# MotorControl_M4.net
KiCad netlist of a schematic drawn in EAGLE
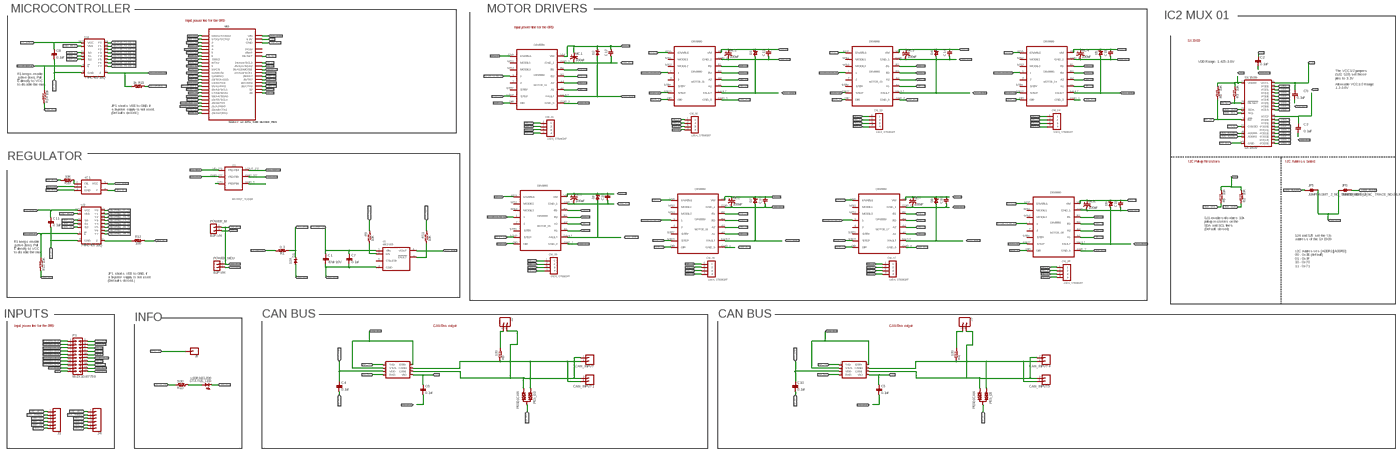
[diagram p0: schematic, sheet 1, overview]
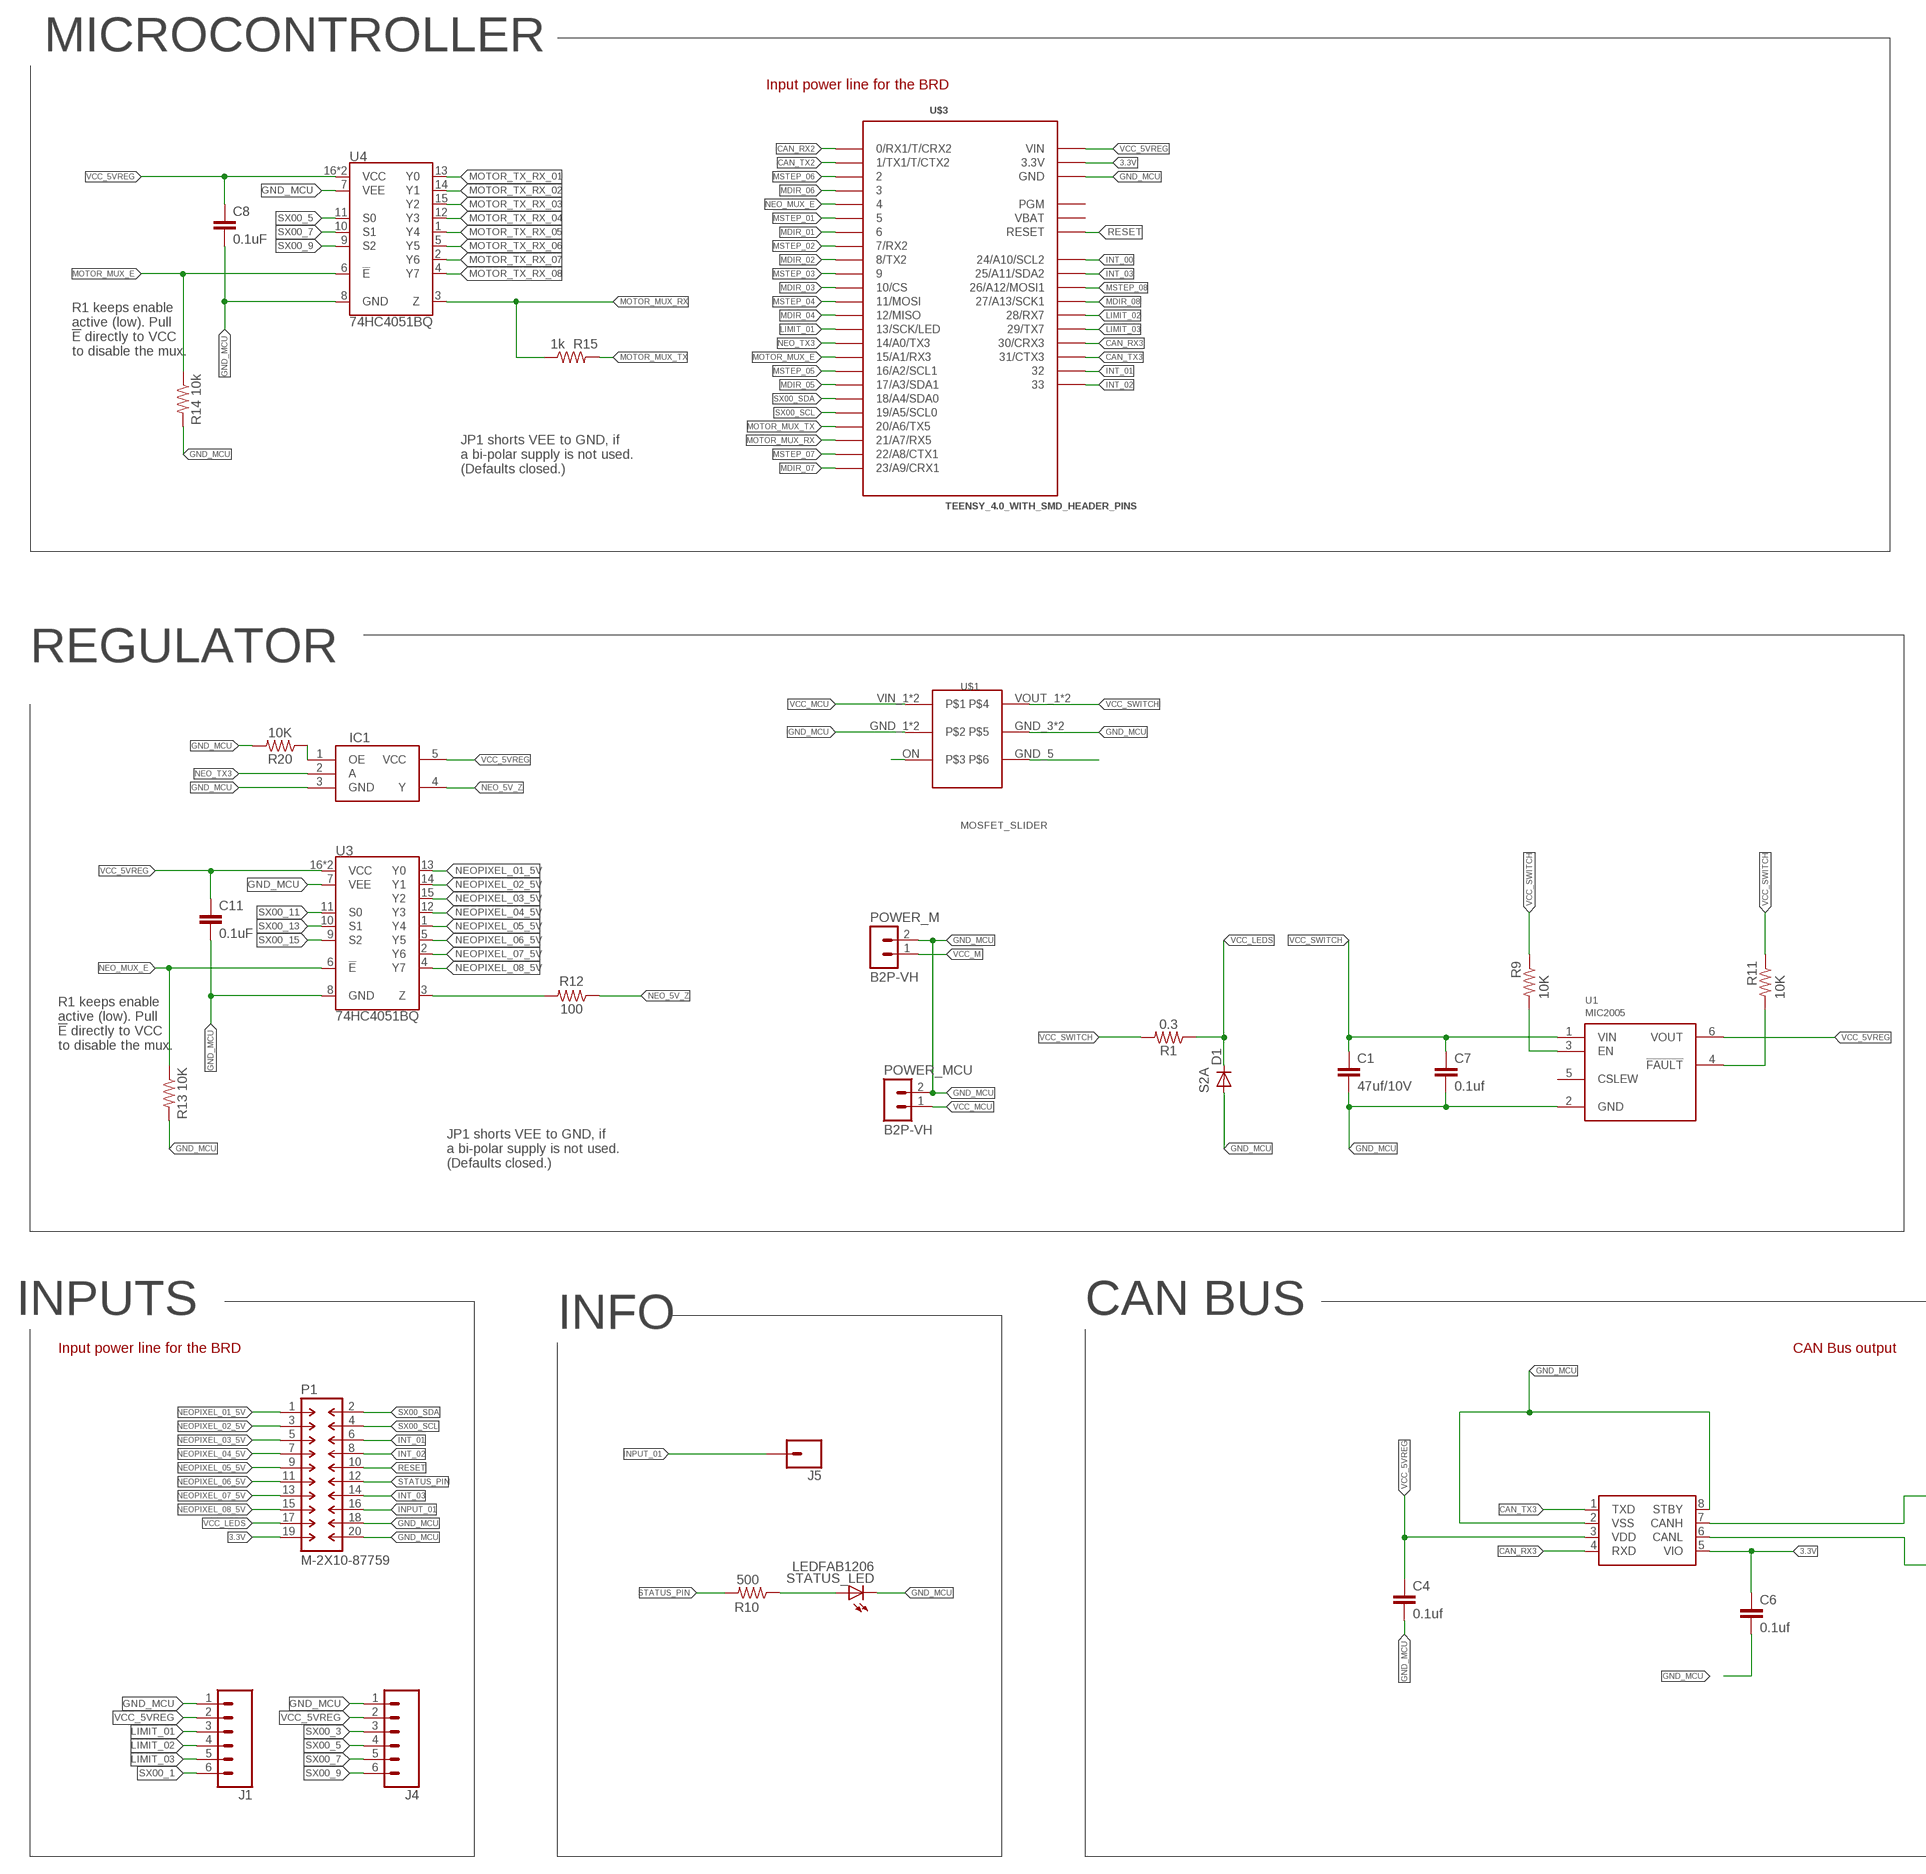
[diagram p1: schematic, sheet 1, part 1 of 4]
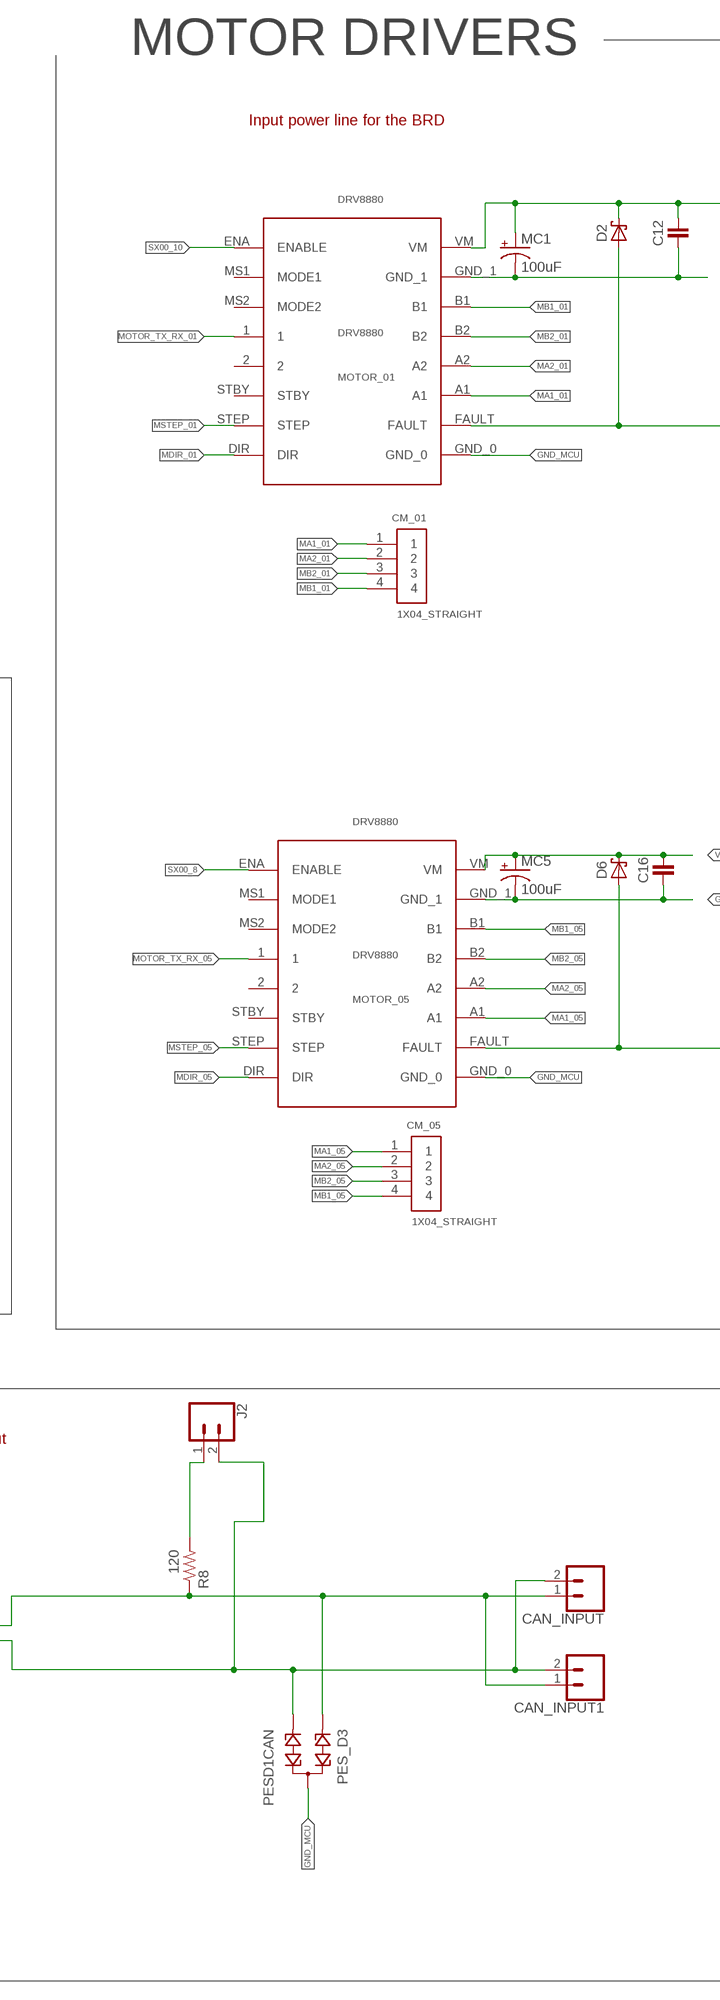
[diagram p2: schematic, sheet 1, part 2 of 4]
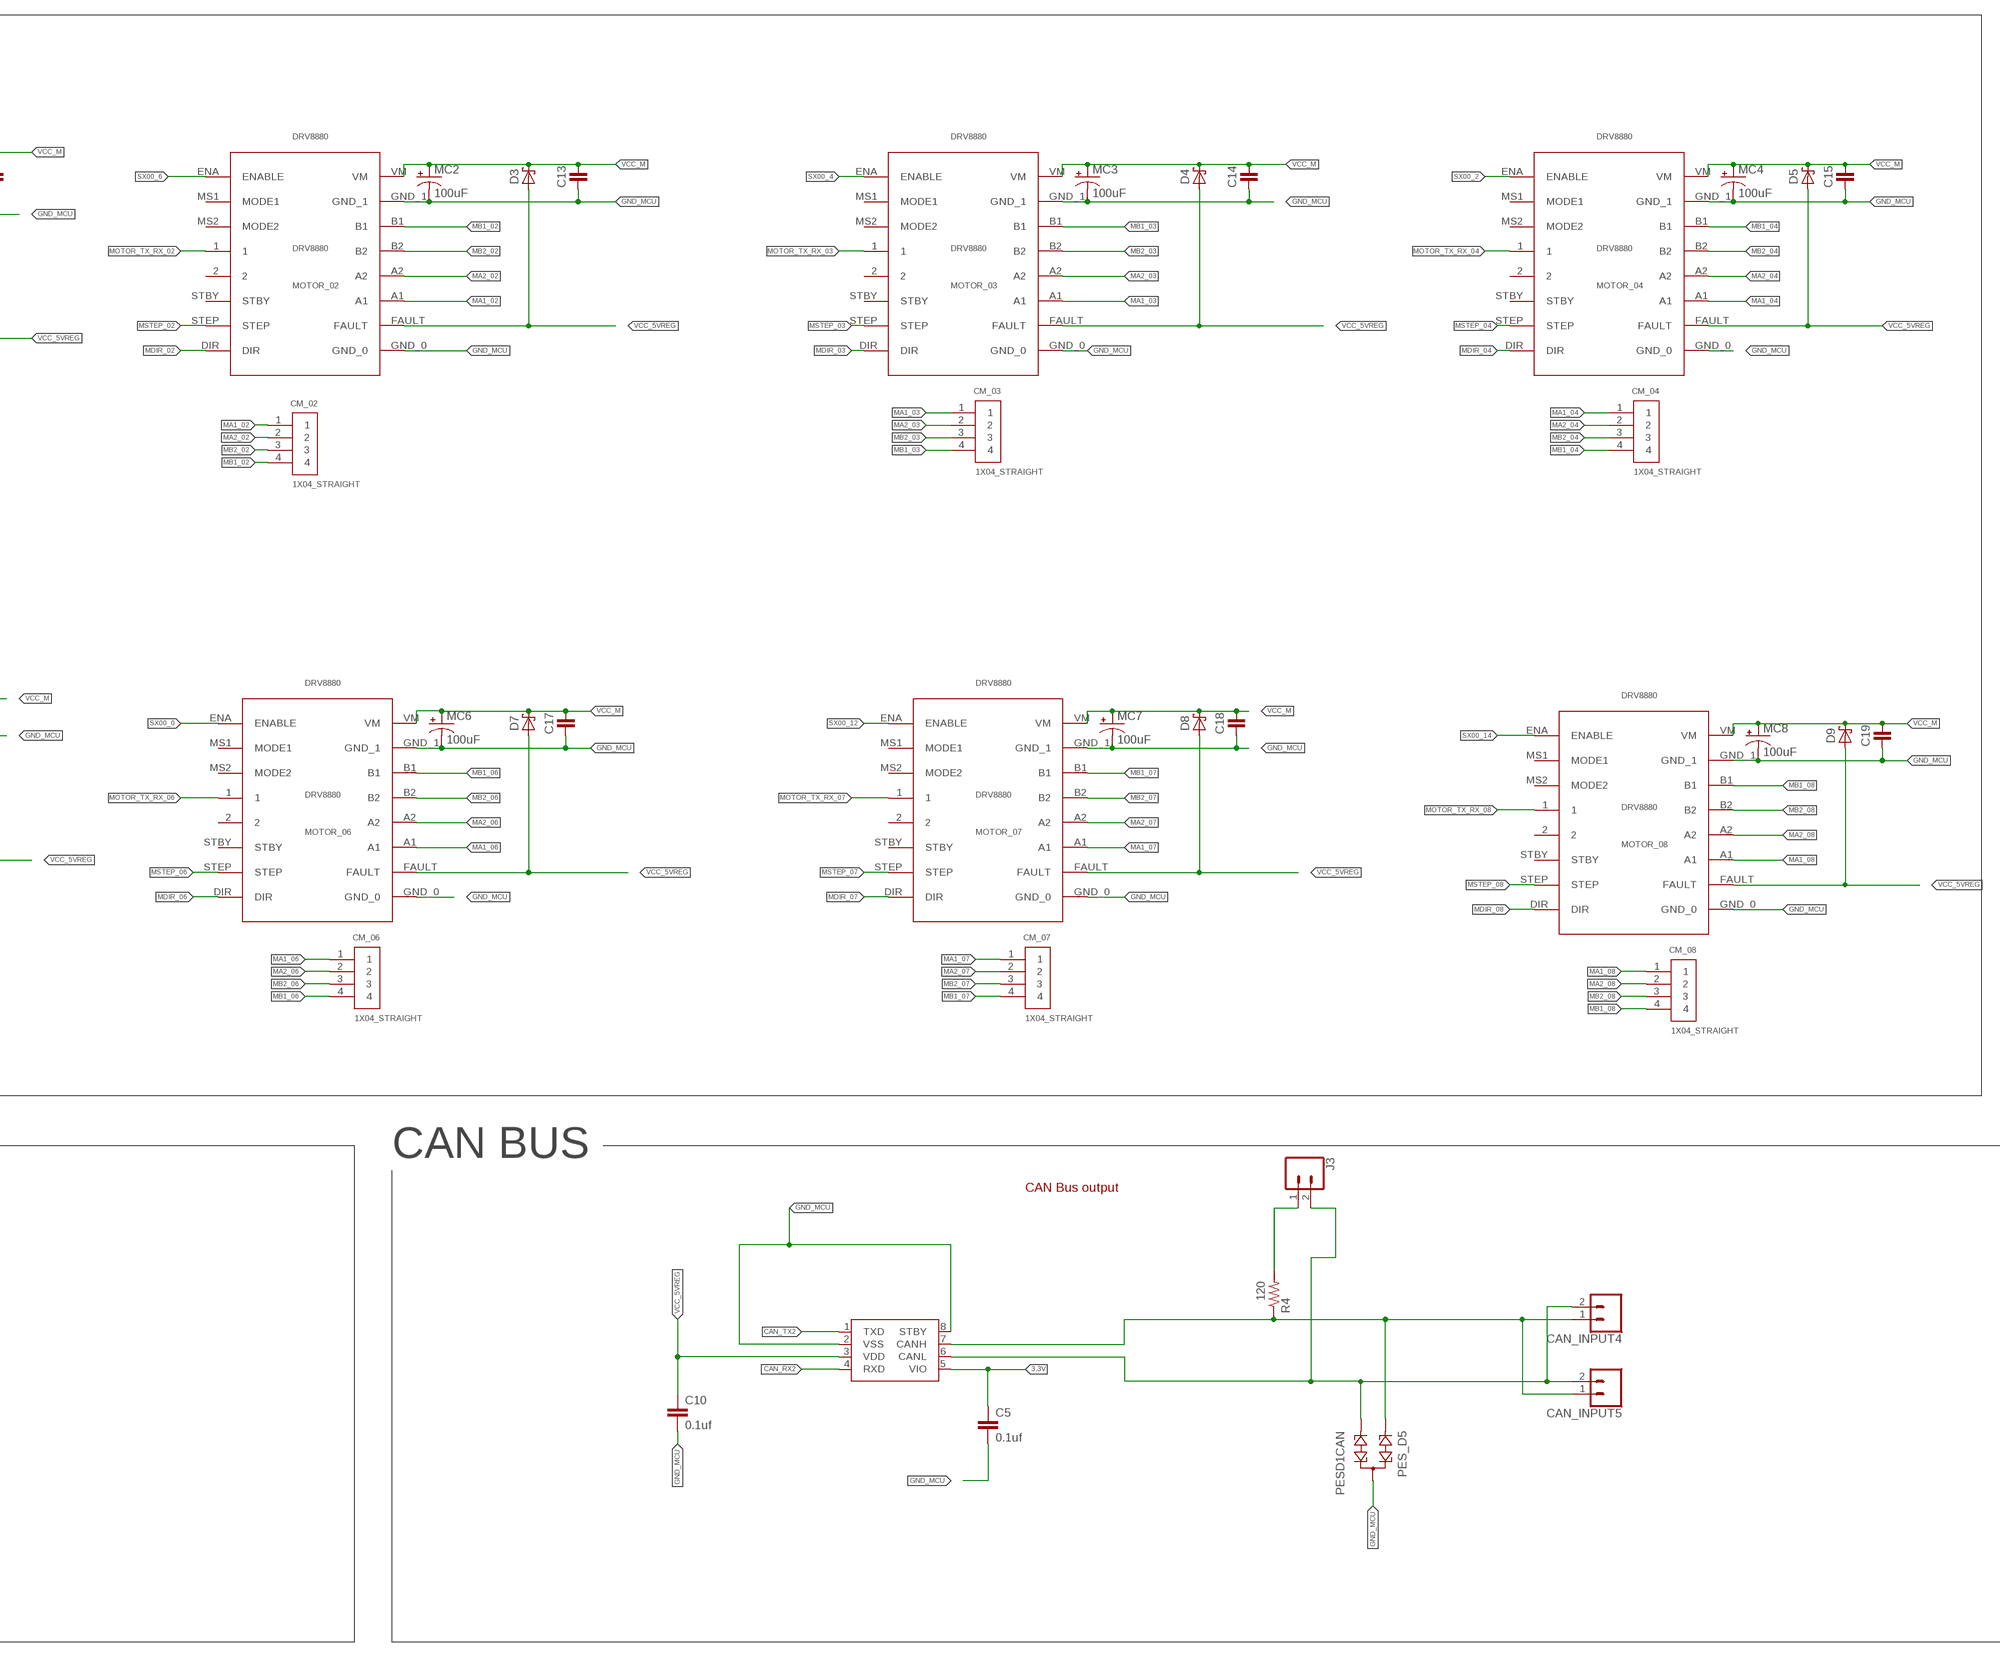
[diagram p3: schematic, sheet 1, part 3 of 4]
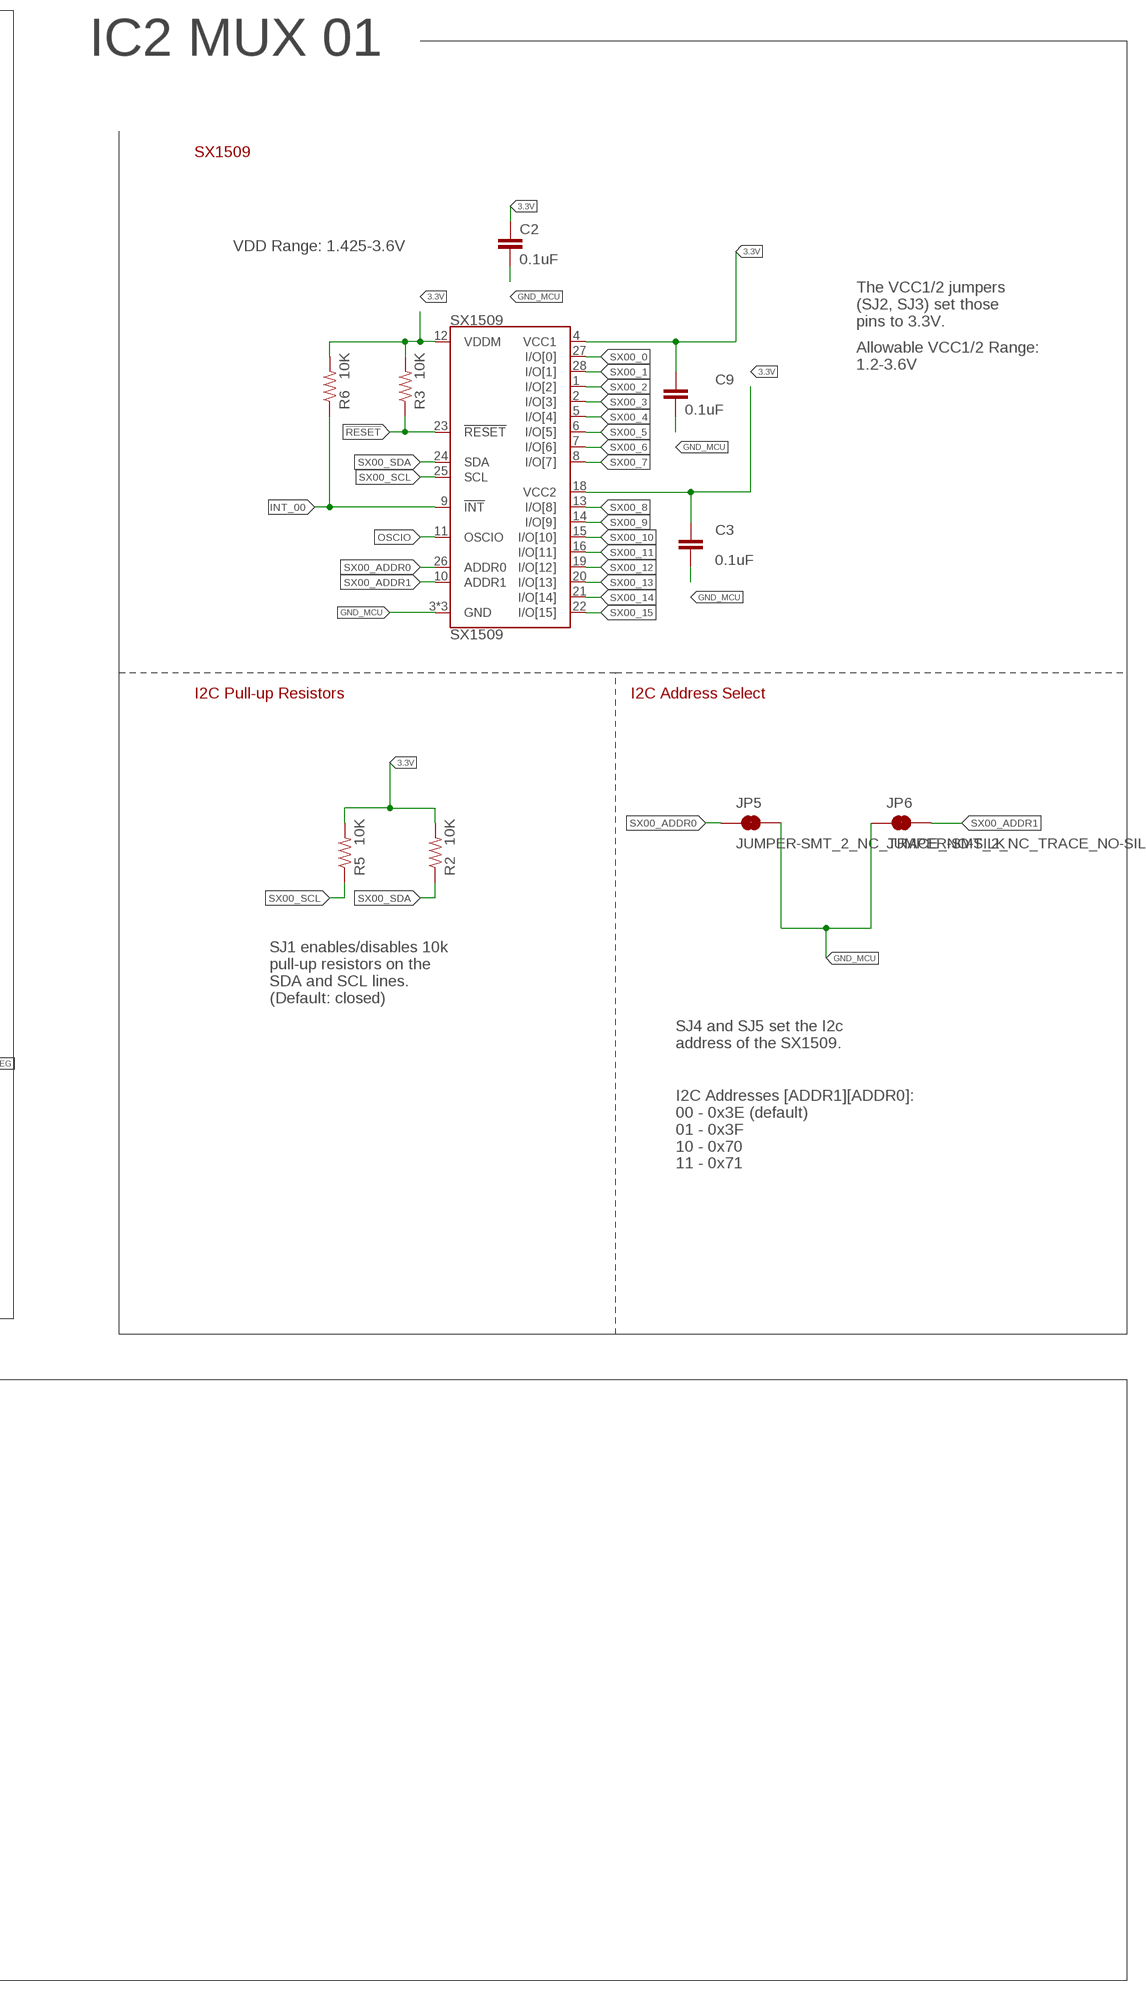
[diagram p4: schematic, sheet 1, part 4 of 4]

(export (version "E")
  (design (tool "Eeschema 10.0.6"))
  (components
    (comp (ref "C1")
      (value "47uf/10V")
      (footprint "eagle-import:0603-CAP")
      (libsource (lib "eagle-import") (part "0.1UF-25V(+80/-20%)(0603)"))
    )
    (comp (ref "C2")
      (value "0.1uF")
      (footprint "eagle-import:0603-CAP")
      (libsource (lib "eagle-import") (part "0.1UF-25V(+80/-20%)(0603)"))
    )
    (comp (ref "C3")
      (value "0.1uF")
      (footprint "eagle-import:0603-CAP")
      (libsource (lib "eagle-import") (part "0.1UF-25V(+80/-20%)(0603)"))
    )
    (comp (ref "C4")
      (value "0.1uf")
      (footprint "eagle-import:0603-CAP")
      (libsource (lib "eagle-import") (part "0.1UF-25V(+80/-20%)(0603)"))
    )
    (comp (ref "C5")
      (value "0.1uf")
      (footprint "eagle-import:0603-CAP")
      (libsource (lib "eagle-import") (part "0.1UF-25V(+80/-20%)(0603)"))
    )
    (comp (ref "C6")
      (value "0.1uf")
      (footprint "eagle-import:0603-CAP")
      (libsource (lib "eagle-import") (part "0.1UF-25V(+80/-20%)(0603)"))
    )
    (comp (ref "C7")
      (value "0.1uf")
      (footprint "eagle-import:0603-CAP")
      (libsource (lib "eagle-import") (part "0.1UF-25V(+80/-20%)(0603)"))
    )
    (comp (ref "C8")
      (value "0.1uF")
      (footprint "eagle-import:0603")
      (libsource (lib "eagle-import") (part "0.1UF-0603-25V-(+80/-20%)"))
    )
    (comp (ref "C9")
      (value "0.1uF")
      (footprint "eagle-import:0603-CAP")
      (libsource (lib "eagle-import") (part "0.1UF-25V(+80/-20%)(0603)"))
    )
    (comp (ref "C10")
      (value "0.1uf")
      (footprint "eagle-import:0603-CAP")
      (libsource (lib "eagle-import") (part "0.1UF-25V(+80/-20%)(0603)"))
    )
    (comp (ref "C11")
      (value "0.1uF")
      (footprint "eagle-import:0603")
      (libsource (lib "eagle-import") (part "0.1UF-0603-25V-(+80/-20%)"))
    )
    (comp (ref "C12")
      (value "CAPACITOR-1210")
      (footprint "eagle-import:C1210")
      (libsource (lib "eagle-import") (part "CAPACITOR-1210"))
    )
    (comp (ref "C13")
      (value "CAPACITOR-1210")
      (footprint "eagle-import:C1210")
      (libsource (lib "eagle-import") (part "CAPACITOR-1210"))
    )
    (comp (ref "C14")
      (value "CAPACITOR-1210")
      (footprint "eagle-import:C1210")
      (libsource (lib "eagle-import") (part "CAPACITOR-1210"))
    )
    (comp (ref "C15")
      (value "CAPACITOR-1210")
      (footprint "eagle-import:C1210")
      (libsource (lib "eagle-import") (part "CAPACITOR-1210"))
    )
    (comp (ref "C16")
      (value "CAPACITOR-1210")
      (footprint "eagle-import:C1210")
      (libsource (lib "eagle-import") (part "CAPACITOR-1210"))
    )
    (comp (ref "C17")
      (value "CAPACITOR-1210")
      (footprint "eagle-import:C1210")
      (libsource (lib "eagle-import") (part "CAPACITOR-1210"))
    )
    (comp (ref "C18")
      (value "CAPACITOR-1210")
      (footprint "eagle-import:C1210")
      (libsource (lib "eagle-import") (part "CAPACITOR-1210"))
    )
    (comp (ref "C19")
      (value "CAPACITOR-1210")
      (footprint "eagle-import:C1210")
      (libsource (lib "eagle-import") (part "CAPACITOR-1210"))
    )
    (comp (ref "CAN_INPUT")
      (value "CONN_02-JST-2MM-SMT")
      (footprint "eagle-import:JST-2-SMD")
      (libsource (lib "eagle-import") (part "CONN_02-JST-2MM-SMT"))
    )
    (comp (ref "CAN_INPUT1")
      (value "CONN_02-JST-2MM-SMT")
      (footprint "eagle-import:JST-2-SMD")
      (libsource (lib "eagle-import") (part "CONN_02-JST-2MM-SMT"))
    )
    (comp (ref "CAN_INPUT4")
      (value "CONN_02-JST-2MM-SMT")
      (footprint "eagle-import:JST-2-SMD")
      (libsource (lib "eagle-import") (part "CONN_02-JST-2MM-SMT"))
    )
    (comp (ref "CAN_INPUT5")
      (value "CONN_02-JST-2MM-SMT")
      (footprint "eagle-import:JST-2-SMD")
      (libsource (lib "eagle-import") (part "CONN_02-JST-2MM-SMT"))
    )
    (comp (ref "CM_01")
      (value "1X04_STRAIGHT")
      (footprint "eagle-import:1X04-CLEANBIG")
      (libsource (lib "eagle-import") (part "1X4-CLEANBIG"))
    )
    (comp (ref "CM_02")
      (value "1X04_STRAIGHT")
      (footprint "eagle-import:1X04-CLEANBIG")
      (libsource (lib "eagle-import") (part "1X4-CLEANBIG"))
    )
    (comp (ref "CM_03")
      (value "1X04_STRAIGHT")
      (footprint "eagle-import:1X04-CLEANBIG")
      (libsource (lib "eagle-import") (part "1X4-CLEANBIG"))
    )
    (comp (ref "CM_04")
      (value "1X04_STRAIGHT")
      (footprint "eagle-import:1X04-CLEANBIG")
      (libsource (lib "eagle-import") (part "1X4-CLEANBIG"))
    )
    (comp (ref "CM_05")
      (value "1X04_STRAIGHT")
      (footprint "eagle-import:1X04-CLEANBIG")
      (libsource (lib "eagle-import") (part "1X4-CLEANBIG"))
    )
    (comp (ref "CM_06")
      (value "1X04_STRAIGHT")
      (footprint "eagle-import:1X04-CLEANBIG")
      (libsource (lib "eagle-import") (part "1X4-CLEANBIG"))
    )
    (comp (ref "CM_07")
      (value "1X04_STRAIGHT")
      (footprint "eagle-import:1X04-CLEANBIG")
      (libsource (lib "eagle-import") (part "1X4-CLEANBIG"))
    )
    (comp (ref "CM_08")
      (value "1X04_STRAIGHT")
      (footprint "eagle-import:1X04-CLEANBIG")
      (libsource (lib "eagle-import") (part "1X4-CLEANBIG"))
    )
    (comp (ref "D1")
      (value "S2A")
      (footprint "eagle-import:DO214AA")
      (fields (field (name "MF") "Fairchild"))
      (libsource (lib "eagle-import") (part "S2A"))
    )
    (comp (ref "D2")
      (value "D_SCHOTTKY-SOD123")
      (footprint "eagle-import:SOD123")
      (libsource (lib "eagle-import") (part "D_SCHOTTKY-SOD123"))
    )
    (comp (ref "D3")
      (value "D_SCHOTTKY-SOD123")
      (footprint "eagle-import:SOD123")
      (libsource (lib "eagle-import") (part "D_SCHOTTKY-SOD123"))
    )
    (comp (ref "D4")
      (value "D_SCHOTTKY-SOD123")
      (footprint "eagle-import:SOD123")
      (libsource (lib "eagle-import") (part "D_SCHOTTKY-SOD123"))
    )
    (comp (ref "D5")
      (value "D_SCHOTTKY-SOD123")
      (footprint "eagle-import:SOD123")
      (libsource (lib "eagle-import") (part "D_SCHOTTKY-SOD123"))
    )
    (comp (ref "D6")
      (value "D_SCHOTTKY-SOD123")
      (footprint "eagle-import:SOD123")
      (libsource (lib "eagle-import") (part "D_SCHOTTKY-SOD123"))
    )
    (comp (ref "D7")
      (value "D_SCHOTTKY-SOD123")
      (footprint "eagle-import:SOD123")
      (libsource (lib "eagle-import") (part "D_SCHOTTKY-SOD123"))
    )
    (comp (ref "D8")
      (value "D_SCHOTTKY-SOD123")
      (footprint "eagle-import:SOD123")
      (libsource (lib "eagle-import") (part "D_SCHOTTKY-SOD123"))
    )
    (comp (ref "D9")
      (value "D_SCHOTTKY-SOD123")
      (footprint "eagle-import:SOD123")
      (libsource (lib "eagle-import") (part "D_SCHOTTKY-SOD123"))
    )
    (comp (ref "IC1")
      (value "74AHC1G125FDBV")
      (footprint "eagle-import:SOT23-5")
      (libsource (lib "eagle-import") (part "741G125FDBVAHC"))
    )
    (comp (ref "J1")
      (value "CONN_06SMD-1MM")
      (footprint "eagle-import:1X06-1MM")
      (libsource (lib "eagle-import") (part "CONN_06SMD-1MM"))
    )
    (comp (ref "J2")
      (value "CONN_02")
      (footprint "eagle-import:1X02")
      (libsource (lib "eagle-import") (part "CONN_02"))
    )
    (comp (ref "J3")
      (value "CONN_02")
      (footprint "eagle-import:1X02")
      (libsource (lib "eagle-import") (part "CONN_02"))
    )
    (comp (ref "J4")
      (value "CONN_06SMD-1MM")
      (footprint "eagle-import:1X06-1MM")
      (libsource (lib "eagle-import") (part "CONN_06SMD-1MM"))
    )
    (comp (ref "J5")
      (value "CONN_01")
      (footprint "eagle-import:1X01")
      (libsource (lib "eagle-import") (part "CONN_01"))
    )
    (comp (ref "JP5")
      (value "JUMPER-SMT_2_NC_TRACE_NO-SILK")
      (footprint "eagle-import:SMT-JUMPER_2_NC_TRACE_NO-SILK")
      (libsource (lib "eagle-import") (part "JUMPER-SMT_2_NC_TRACE_NO-SILK"))
    )
    (comp (ref "JP6")
      (value "JUMPER-SMT_2_NC_TRACE_NO-SILK")
      (footprint "eagle-import:SMT-JUMPER_2_NC_TRACE_NO-SILK")
      (libsource (lib "eagle-import") (part "JUMPER-SMT_2_NC_TRACE_NO-SILK"))
    )
    (comp (ref "MC1")
      (value "100uF")
      (footprint "eagle-import:PANASONIC_D")
      (libsource (lib "eagle-import") (part "100UF-POLAR-25V-20%(ELEC)"))
    )
    (comp (ref "MC2")
      (value "100uF")
      (footprint "eagle-import:PANASONIC_D")
      (libsource (lib "eagle-import") (part "100UF-POLAR-25V-20%(ELEC)"))
    )
    (comp (ref "MC3")
      (value "100uF")
      (footprint "eagle-import:PANASONIC_D")
      (libsource (lib "eagle-import") (part "100UF-POLAR-25V-20%(ELEC)"))
    )
    (comp (ref "MC4")
      (value "100uF")
      (footprint "eagle-import:PANASONIC_D")
      (libsource (lib "eagle-import") (part "100UF-POLAR-25V-20%(ELEC)"))
    )
    (comp (ref "MC5")
      (value "100uF")
      (footprint "eagle-import:PANASONIC_D")
      (libsource (lib "eagle-import") (part "100UF-POLAR-25V-20%(ELEC)"))
    )
    (comp (ref "MC6")
      (value "100uF")
      (footprint "eagle-import:PANASONIC_D")
      (libsource (lib "eagle-import") (part "100UF-POLAR-25V-20%(ELEC)"))
    )
    (comp (ref "MC7")
      (value "100uF")
      (footprint "eagle-import:PANASONIC_D")
      (libsource (lib "eagle-import") (part "100UF-POLAR-25V-20%(ELEC)"))
    )
    (comp (ref "MC8")
      (value "100uF")
      (footprint "eagle-import:PANASONIC_D")
      (libsource (lib "eagle-import") (part "100UF-POLAR-25V-20%(ELEC)"))
    )
    (comp (ref "MCP2562FD")
      (value "MCP2562-E/SN")
      (footprint "eagle-import:SOIC127P600X175-8N")
      (fields (field (name "MF") "Microchip"))
      (libsource (lib "eagle-import") (part "MCP2562-E/SN"))
    )
    (comp (ref "MCP2562_2.0")
      (value "MCP2562-E/SN")
      (footprint "eagle-import:SOIC127P600X175-8N")
      (fields (field (name "MF") "Microchip"))
      (libsource (lib "eagle-import") (part "MCP2562-E/SN"))
    )
    (comp (ref "MOTOR_01")
      (value "DRV8880")
      (footprint "eagle-import:DRV8880")
      (libsource (lib "eagle-import") (part "DRV8880"))
    )
    (comp (ref "MOTOR_02")
      (value "DRV8880")
      (footprint "eagle-import:DRV8880")
      (libsource (lib "eagle-import") (part "DRV8880"))
    )
    (comp (ref "MOTOR_03")
      (value "DRV8880")
      (footprint "eagle-import:DRV8880")
      (libsource (lib "eagle-import") (part "DRV8880"))
    )
    (comp (ref "MOTOR_04")
      (value "DRV8880")
      (footprint "eagle-import:DRV8880")
      (libsource (lib "eagle-import") (part "DRV8880"))
    )
    (comp (ref "MOTOR_05")
      (value "DRV8880")
      (footprint "eagle-import:DRV8880")
      (libsource (lib "eagle-import") (part "DRV8880"))
    )
    (comp (ref "MOTOR_06")
      (value "DRV8880")
      (footprint "eagle-import:DRV8880")
      (libsource (lib "eagle-import") (part "DRV8880"))
    )
    (comp (ref "MOTOR_07")
      (value "DRV8880")
      (footprint "eagle-import:DRV8880")
      (libsource (lib "eagle-import") (part "DRV8880"))
    )
    (comp (ref "MOTOR_08")
      (value "DRV8880")
      (footprint "eagle-import:DRV8880")
      (libsource (lib "eagle-import") (part "DRV8880"))
    )
    (comp (ref "P1")
      (value "M-2X10-87759")
      (footprint "eagle-import:87759-20")
      (libsource (lib "eagle-import") (part "M-2X10-87759"))
    )
    (comp (ref "PES_D3")
      (value "PESD1CAN")
      (footprint "eagle-import:SOT23")
      (libsource (lib "eagle-import") (part "PESD1CAN"))
    )
    (comp (ref "PES_D5")
      (value "PESD1CAN")
      (footprint "eagle-import:SOT23")
      (libsource (lib "eagle-import") (part "PESD1CAN"))
    )
    (comp (ref "POWER_M")
      (value "B2P-VH")
      (footprint "eagle-import:B2P-VH")
      (libsource (lib "eagle-import") (part "B2P-VH"))
    )
    (comp (ref "POWER_MCU")
      (value "B2P-VH")
      (footprint "eagle-import:B2P-VH")
      (libsource (lib "eagle-import") (part "B2P-VH"))
    )
    (comp (ref "R1")
      (value "0.3")
      (footprint "eagle-import:0805")
      (libsource (lib "eagle-import") (part "0.3OHM-0805-1/8W-1%"))
    )
    (comp (ref "R2")
      (value "10K")
      (footprint "eagle-import:0603-RES")
      (libsource (lib "eagle-import") (part "10KOHM-1/10W-1%(0603)0603"))
    )
    (comp (ref "R3")
      (value "10K")
      (footprint "eagle-import:0603-RES")
      (libsource (lib "eagle-import") (part "10KOHM-1/10W-1%(0603)0603"))
    )
    (comp (ref "R4")
      (value "120")
      (footprint "eagle-import:0603-RES")
      (libsource (lib "eagle-import") (part "SparkFun-Resistors_532_10KOHM-1/10W-1%(0603)0603"))
    )
    (comp (ref "R5")
      (value "10K")
      (footprint "eagle-import:0603-RES")
      (libsource (lib "eagle-import") (part "10KOHM-1/10W-1%(0603)0603"))
    )
    (comp (ref "R6")
      (value "10K")
      (footprint "eagle-import:0603-RES")
      (libsource (lib "eagle-import") (part "10KOHM-1/10W-1%(0603)0603"))
    )
    (comp (ref "R8")
      (value "120")
      (footprint "eagle-import:0603-RES")
      (libsource (lib "eagle-import") (part "SparkFun-Resistors_532_10KOHM-1/10W-1%(0603)0603"))
    )
    (comp (ref "R9")
      (value "10K")
      (footprint "eagle-import:0603-RES")
      (libsource (lib "eagle-import") (part "SparkFun-Resistors_532_10KOHM-1/10W-1%(0603)0603"))
    )
    (comp (ref "R10")
      (value "500")
      (footprint "eagle-import:0603-RES")
      (libsource (lib "eagle-import") (part "SparkFun-Resistors_532_10KOHM-1/10W-1%(0603)0603"))
    )
    (comp (ref "R11")
      (value "10K")
      (footprint "eagle-import:0603-RES")
      (libsource (lib "eagle-import") (part "SparkFun-Resistors_532_10KOHM-1/10W-1%(0603)0603"))
    )
    (comp (ref "R12")
      (value "100")
      (footprint "eagle-import:0603")
      (libsource (lib "eagle-import") (part "10KOHM-0603-1/10W-1%"))
    )
    (comp (ref "R13")
      (value "10K")
      (footprint "eagle-import:0603")
      (libsource (lib "eagle-import") (part "10KOHM-0603-1/10W-1%"))
    )
    (comp (ref "R14")
      (value "10k")
      (footprint "eagle-import:0603")
      (libsource (lib "eagle-import") (part "10KOHM-0603-1/10W-1%"))
    )
    (comp (ref "R15")
      (value "1k")
      (footprint "eagle-import:0603")
      (libsource (lib "eagle-import") (part "10KOHM-0603-1/10W-1%"))
    )
    (comp (ref "R20")
      (value "10K")
      (footprint "eagle-import:0805")
      (libsource (lib "eagle-import") (part "0.3OHM-0805-1/8W-1%"))
    )
    (comp (ref "STATUS_LED")
      (value "LEDFAB1206")
      (footprint "eagle-import:LED1206FAB")
      (libsource (lib "eagle-import") (part "LEDFAB1206"))
    )
    (comp (ref "SX1509")
      (value "SX1509")
      (footprint "eagle-import:QFN-28")
      (libsource (lib "eagle-import") (part "SX1509"))
    )
    (comp (ref "U$1")
      (value "MOSFET_SLIDER")
      (footprint "eagle-import:MOSFET_SLIDER")
      (libsource (lib "eagle-import") (part "MOSFET_SLIDER"))
    )
    (comp (ref "U$3")
      (value "TEENSY_4.0_WITH_SMD_HEADER_PINS")
      (footprint "eagle-import:TEENSY_4.0_WITH_SMD_HEADER_PINS")
      (libsource (lib "eagle-import") (part "TEENSY_4.0_WITH_SMD_HEADER_PINS"))
    )
    (comp (ref "U1")
      (value "MIC2005")
      (footprint "eagle-import:SOT23-6")
      (libsource (lib "eagle-import") (part "MIC2050"))
    )
    (comp (ref "U3")
      (value "74HC4051BQ")
      (footprint "eagle-import:DHVQFN-16-2.5X3.5MM")
      (libsource (lib "eagle-import") (part "74HC4051BQ"))
    )
    (comp (ref "U4")
      (value "74HC4051BQ")
      (footprint "eagle-import:DHVQFN-16-2.5X3.5MM")
      (libsource (lib "eagle-import") (part "74HC4051BQ"))
    )
  )
  (nets
    (net (code "1") (name "3.3V") (class "Default")
      (node (ref "C2") (pin "1") (pinfunction "1_1") (pintype "passive"))
      (node (ref "C3") (pin "1") (pinfunction "1_1") (pintype "passive"))
      (node (ref "C5") (pin "1") (pinfunction "1_1") (pintype "passive"))
      (node (ref "C6") (pin "1") (pinfunction "1_1") (pintype "passive"))
      (node (ref "C9") (pin "1") (pinfunction "1_1") (pintype "passive"))
      (node (ref "MCP2562FD") (pin "5") (pinfunction "VIO_5") (pintype "power_in"))
      (node (ref "MCP2562_2.0") (pin "5") (pinfunction "VIO_5") (pintype "power_in"))
      (node (ref "P1") (pin "19") (pinfunction "19_19") (pintype "passive"))
      (node (ref "R2") (pin "2") (pinfunction "2_2") (pintype "passive"))
      (node (ref "R3") (pin "2") (pinfunction "2_2") (pintype "passive"))
      (node (ref "R5") (pin "2") (pinfunction "2_2") (pintype "passive"))
      (node (ref "R6") (pin "2") (pinfunction "2_2") (pintype "passive"))
      (node (ref "SX1509") (pin "12") (pinfunction "VDDM_12") (pintype "bidirectional"))
      (node (ref "SX1509") (pin "18") (pinfunction "VCC2_18") (pintype "bidirectional"))
      (node (ref "SX1509") (pin "4") (pinfunction "VCC1_4") (pintype "bidirectional"))
      (node (ref "U$3") (pin "3.3V") (pinfunction "3.3V_3.3V") (pintype "power_in"))
      (node (ref "U$3") (pin "3.3V1") (pinfunction "3.3V_3.3V1") (pintype "power_in"))
    )
    (net (code "2") (name "CAN_RX2") (class "Default")
      (node (ref "MCP2562_2.0") (pin "4") (pinfunction "RXD_4") (pintype "output"))
      (node (ref "U$3") (pin "0") (pinfunction "0/RX1/T/CRX2_0") (pintype "bidirectional"))
    )
    (net (code "3") (name "CAN_RX3") (class "Default")
      (node (ref "MCP2562FD") (pin "4") (pinfunction "RXD_4") (pintype "output"))
      (node (ref "U$3") (pin "30") (pinfunction "30/CRX3_30") (pintype "bidirectional"))
    )
    (net (code "4") (name "CAN_TX2") (class "Default")
      (node (ref "MCP2562_2.0") (pin "1") (pinfunction "TXD_1") (pintype "input"))
      (node (ref "U$3") (pin "1") (pinfunction "1/TX1/T/CTX2_1") (pintype "bidirectional"))
    )
    (net (code "5") (name "CAN_TX3") (class "Default")
      (node (ref "MCP2562FD") (pin "1") (pinfunction "TXD_1") (pintype "input"))
      (node (ref "U$3") (pin "31") (pinfunction "31/CTX3_31") (pintype "bidirectional"))
    )
    (net (code "6") (name "GND_MCU") (class "Default")
      (node (ref "C1") (pin "2") (pinfunction "2_2") (pintype "passive"))
      (node (ref "C10") (pin "2") (pinfunction "2_2") (pintype "passive"))
      (node (ref "C11") (pin "2") (pinfunction "2_2") (pintype "passive"))
      (node (ref "C12") (pin "1") (pinfunction "1_1") (pintype "passive"))
      (node (ref "C13") (pin "1") (pinfunction "1_1") (pintype "passive"))
      (node (ref "C14") (pin "1") (pinfunction "1_1") (pintype "passive"))
      (node (ref "C15") (pin "1") (pinfunction "1_1") (pintype "passive"))
      (node (ref "C16") (pin "1") (pinfunction "1_1") (pintype "passive"))
      (node (ref "C17") (pin "1") (pinfunction "1_1") (pintype "passive"))
      (node (ref "C18") (pin "1") (pinfunction "1_1") (pintype "passive"))
      (node (ref "C19") (pin "1") (pinfunction "1_1") (pintype "passive"))
      (node (ref "C2") (pin "2") (pinfunction "2_2") (pintype "passive"))
      (node (ref "C3") (pin "2") (pinfunction "2_2") (pintype "passive"))
      (node (ref "C4") (pin "2") (pinfunction "2_2") (pintype "passive"))
      (node (ref "C5") (pin "2") (pinfunction "2_2") (pintype "passive"))
      (node (ref "C6") (pin "2") (pinfunction "2_2") (pintype "passive"))
      (node (ref "C7") (pin "2") (pinfunction "2_2") (pintype "passive"))
      (node (ref "C8") (pin "2") (pinfunction "2_2") (pintype "passive"))
      (node (ref "C9") (pin "2") (pinfunction "2_2") (pintype "passive"))
      (node (ref "D1") (pin "A") (pinfunction "A_A") (pintype "passive"))
      (node (ref "IC1") (pin "3") (pinfunction "GND_3") (pintype "bidirectional"))
      (node (ref "J1") (pin "1") (pinfunction "1_1") (pintype "passive"))
      (node (ref "J4") (pin "1") (pinfunction "1_1") (pintype "passive"))
      (node (ref "JP5") (pin "2") (pinfunction "2_2") (pintype "passive"))
      (node (ref "JP6") (pin "1") (pinfunction "1_1") (pintype "passive"))
      (node (ref "MC1") (pin "-") (pinfunction "-_-") (pintype "passive"))
      (node (ref "MC2") (pin "-") (pinfunction "-_-") (pintype "passive"))
      (node (ref "MC3") (pin "-") (pinfunction "-_-") (pintype "passive"))
      (node (ref "MC4") (pin "-") (pinfunction "-_-") (pintype "passive"))
      (node (ref "MC5") (pin "-") (pinfunction "-_-") (pintype "passive"))
      (node (ref "MC6") (pin "-") (pinfunction "-_-") (pintype "passive"))
      (node (ref "MC7") (pin "-") (pinfunction "-_-") (pintype "passive"))
      (node (ref "MC8") (pin "-") (pinfunction "-_-") (pintype "passive"))
      (node (ref "MCP2562FD") (pin "2") (pinfunction "VSS_2") (pintype "power_in"))
      (node (ref "MCP2562FD") (pin "8") (pinfunction "STBY_8") (pintype "input"))
      (node (ref "MCP2562_2.0") (pin "2") (pinfunction "VSS_2") (pintype "power_in"))
      (node (ref "MCP2562_2.0") (pin "8") (pinfunction "STBY_8") (pintype "input"))
      (node (ref "MOTOR_01") (pin "GND_0") (pinfunction "GND_0_GND_0") (pintype "bidirectional"))
      (node (ref "MOTOR_01") (pin "GND_1") (pinfunction "GND_1_GND_1") (pintype "bidirectional"))
      (node (ref "MOTOR_02") (pin "GND_0") (pinfunction "GND_0_GND_0") (pintype "bidirectional"))
      (node (ref "MOTOR_02") (pin "GND_1") (pinfunction "GND_1_GND_1") (pintype "bidirectional"))
      (node (ref "MOTOR_03") (pin "GND_0") (pinfunction "GND_0_GND_0") (pintype "bidirectional"))
      (node (ref "MOTOR_03") (pin "GND_1") (pinfunction "GND_1_GND_1") (pintype "bidirectional"))
      (node (ref "MOTOR_04") (pin "GND_0") (pinfunction "GND_0_GND_0") (pintype "bidirectional"))
      (node (ref "MOTOR_04") (pin "GND_1") (pinfunction "GND_1_GND_1") (pintype "bidirectional"))
      (node (ref "MOTOR_05") (pin "GND_0") (pinfunction "GND_0_GND_0") (pintype "bidirectional"))
      (node (ref "MOTOR_05") (pin "GND_1") (pinfunction "GND_1_GND_1") (pintype "bidirectional"))
      (node (ref "MOTOR_06") (pin "GND_0") (pinfunction "GND_0_GND_0") (pintype "bidirectional"))
      (node (ref "MOTOR_06") (pin "GND_1") (pinfunction "GND_1_GND_1") (pintype "bidirectional"))
      (node (ref "MOTOR_07") (pin "GND_0") (pinfunction "GND_0_GND_0") (pintype "bidirectional"))
      (node (ref "MOTOR_07") (pin "GND_1") (pinfunction "GND_1_GND_1") (pintype "bidirectional"))
      (node (ref "MOTOR_08") (pin "GND_0") (pinfunction "GND_0_GND_0") (pintype "bidirectional"))
      (node (ref "MOTOR_08") (pin "GND_1") (pinfunction "GND_1_GND_1") (pintype "bidirectional"))
      (node (ref "P1") (pin "18") (pinfunction "18_18") (pintype "passive"))
      (node (ref "P1") (pin "20") (pinfunction "20_20") (pintype "passive"))
      (node (ref "PES_D3") (pin "3") (pinfunction "3_3") (pintype "passive"))
      (node (ref "PES_D5") (pin "3") (pinfunction "3_3") (pintype "passive"))
      (node (ref "POWER_M") (pin "2") (pinfunction "2_2") (pintype "passive"))
      (node (ref "POWER_MCU") (pin "2") (pinfunction "2_2") (pintype "passive"))
      (node (ref "R13") (pin "2") (pinfunction "2_2") (pintype "passive"))
      (node (ref "R14") (pin "2") (pinfunction "2_2") (pintype "passive"))
      (node (ref "R20") (pin "2") (pinfunction "2_2") (pintype "passive"))
      (node (ref "STATUS_LED") (pin "2") (pinfunction "C_2") (pintype "passive"))
      (node (ref "SX1509") (pin "17") (pinfunction "GND_17") (pintype "bidirectional"))
      (node (ref "SX1509") (pin "29") (pinfunction "GND_29") (pintype "bidirectional"))
      (node (ref "SX1509") (pin "3") (pinfunction "GND_3") (pintype "bidirectional"))
      (node (ref "U$1") (pin "GND_1") (pinfunction "P$2_GND_1") (pintype "bidirectional"))
      (node (ref "U$1") (pin "GND_2") (pinfunction "P$2_GND_2") (pintype "bidirectional"))
      (node (ref "U$1") (pin "GND_3") (pinfunction "P$5_GND_3") (pintype "bidirectional"))
      (node (ref "U$1") (pin "GND_4") (pinfunction "P$5_GND_4") (pintype "bidirectional"))
      (node (ref "U$3") (pin "GND") (pinfunction "GND_GND") (pintype "power_in"))
      (node (ref "U$3") (pin "GND1") (pinfunction "GND_GND1") (pintype "power_in"))
      (node (ref "U$3") (pin "GND2") (pinfunction "GND_GND2") (pintype "power_in"))
      (node (ref "U1") (pin "2") (pinfunction "GND_2") (pintype "bidirectional"))
      (node (ref "U3") (pin "7") (pinfunction "VEE_7") (pintype "bidirectional"))
      (node (ref "U3") (pin "8") (pinfunction "GND_8") (pintype "bidirectional"))
      (node (ref "U4") (pin "7") (pinfunction "VEE_7") (pintype "bidirectional"))
      (node (ref "U4") (pin "8") (pinfunction "GND_8") (pintype "bidirectional"))
    )
    (net (code "7") (name "INPUT_01") (class "Default")
      (node (ref "J5") (pin "1") (pinfunction "1_1") (pintype "passive"))
      (node (ref "P1") (pin "16") (pinfunction "16_16") (pintype "passive"))
    )
    (net (code "8") (name "INT_00") (class "Default")
      (node (ref "R6") (pin "1") (pinfunction "1_1") (pintype "passive"))
      (node (ref "SX1509") (pin "9") (pinfunction "~{INT}_9") (pintype "bidirectional"))
      (node (ref "U$3") (pin "24") (pinfunction "24/A10/SCL2_24") (pintype "bidirectional"))
    )
    (net (code "9") (name "INT_01") (class "Default")
      (node (ref "P1") (pin "6") (pinfunction "6_6") (pintype "passive"))
      (node (ref "U$3") (pin "32") (pinfunction "32_32") (pintype "bidirectional"))
    )
    (net (code "10") (name "INT_02") (class "Default")
      (node (ref "P1") (pin "8") (pinfunction "8_8") (pintype "passive"))
      (node (ref "U$3") (pin "33") (pinfunction "33_33") (pintype "bidirectional"))
    )
    (net (code "11") (name "INT_03") (class "Default")
      (node (ref "P1") (pin "14") (pinfunction "14_14") (pintype "passive"))
      (node (ref "U$3") (pin "25") (pinfunction "25/A11/SDA2_25") (pintype "bidirectional"))
    )
    (net (code "12") (name "LIMIT_01") (class "Default")
      (node (ref "J1") (pin "3") (pinfunction "3_3") (pintype "passive"))
      (node (ref "U$3") (pin "13") (pinfunction "13/SCK/LED_13") (pintype "bidirectional"))
    )
    (net (code "13") (name "LIMIT_02") (class "Default")
      (node (ref "J1") (pin "4") (pinfunction "4_4") (pintype "passive"))
      (node (ref "U$3") (pin "28") (pinfunction "28/RX7_28") (pintype "bidirectional"))
    )
    (net (code "14") (name "LIMIT_03") (class "Default")
      (node (ref "J1") (pin "5") (pinfunction "5_5") (pintype "passive"))
      (node (ref "U$3") (pin "29") (pinfunction "29/TX7_29") (pintype "bidirectional"))
    )
    (net (code "15") (name "MA1_01") (class "Default")
      (node (ref "CM_01") (pin "1") (pinfunction "1_1") (pintype "bidirectional"))
      (node (ref "MOTOR_01") (pin "A1") (pinfunction "A1_A1") (pintype "bidirectional"))
    )
    (net (code "16") (name "MA1_02") (class "Default")
      (node (ref "CM_02") (pin "1") (pinfunction "1_1") (pintype "bidirectional"))
      (node (ref "MOTOR_02") (pin "A1") (pinfunction "A1_A1") (pintype "bidirectional"))
    )
    (net (code "17") (name "MA1_03") (class "Default")
      (node (ref "CM_03") (pin "1") (pinfunction "1_1") (pintype "bidirectional"))
      (node (ref "MOTOR_03") (pin "A1") (pinfunction "A1_A1") (pintype "bidirectional"))
    )
    (net (code "18") (name "MA1_04") (class "Default")
      (node (ref "CM_04") (pin "1") (pinfunction "1_1") (pintype "bidirectional"))
      (node (ref "MOTOR_04") (pin "A1") (pinfunction "A1_A1") (pintype "bidirectional"))
    )
    (net (code "19") (name "MA1_05") (class "Default")
      (node (ref "CM_05") (pin "1") (pinfunction "1_1") (pintype "bidirectional"))
      (node (ref "MOTOR_05") (pin "A1") (pinfunction "A1_A1") (pintype "bidirectional"))
    )
    (net (code "20") (name "MA1_06") (class "Default")
      (node (ref "CM_06") (pin "1") (pinfunction "1_1") (pintype "bidirectional"))
      (node (ref "MOTOR_06") (pin "A1") (pinfunction "A1_A1") (pintype "bidirectional"))
    )
    (net (code "21") (name "MA1_07") (class "Default")
      (node (ref "CM_07") (pin "1") (pinfunction "1_1") (pintype "bidirectional"))
      (node (ref "MOTOR_07") (pin "A1") (pinfunction "A1_A1") (pintype "bidirectional"))
    )
    (net (code "22") (name "MA1_08") (class "Default")
      (node (ref "CM_08") (pin "1") (pinfunction "1_1") (pintype "bidirectional"))
      (node (ref "MOTOR_08") (pin "A1") (pinfunction "A1_A1") (pintype "bidirectional"))
    )
    (net (code "23") (name "MA2_01") (class "Default")
      (node (ref "CM_01") (pin "2") (pinfunction "2_2") (pintype "bidirectional"))
      (node (ref "MOTOR_01") (pin "A2") (pinfunction "A2_A2") (pintype "bidirectional"))
    )
    (net (code "24") (name "MA2_02") (class "Default")
      (node (ref "CM_02") (pin "2") (pinfunction "2_2") (pintype "bidirectional"))
      (node (ref "MOTOR_02") (pin "A2") (pinfunction "A2_A2") (pintype "bidirectional"))
    )
    (net (code "25") (name "MA2_03") (class "Default")
      (node (ref "CM_03") (pin "2") (pinfunction "2_2") (pintype "bidirectional"))
      (node (ref "MOTOR_03") (pin "A2") (pinfunction "A2_A2") (pintype "bidirectional"))
    )
    (net (code "26") (name "MA2_04") (class "Default")
      (node (ref "CM_04") (pin "2") (pinfunction "2_2") (pintype "bidirectional"))
      (node (ref "MOTOR_04") (pin "A2") (pinfunction "A2_A2") (pintype "bidirectional"))
    )
    (net (code "27") (name "MA2_05") (class "Default")
      (node (ref "CM_05") (pin "2") (pinfunction "2_2") (pintype "bidirectional"))
      (node (ref "MOTOR_05") (pin "A2") (pinfunction "A2_A2") (pintype "bidirectional"))
    )
    (net (code "28") (name "MA2_06") (class "Default")
      (node (ref "CM_06") (pin "2") (pinfunction "2_2") (pintype "bidirectional"))
      (node (ref "MOTOR_06") (pin "A2") (pinfunction "A2_A2") (pintype "bidirectional"))
    )
    (net (code "29") (name "MA2_07") (class "Default")
      (node (ref "CM_07") (pin "2") (pinfunction "2_2") (pintype "bidirectional"))
      (node (ref "MOTOR_07") (pin "A2") (pinfunction "A2_A2") (pintype "bidirectional"))
    )
    (net (code "30") (name "MA2_08") (class "Default")
      (node (ref "CM_08") (pin "2") (pinfunction "2_2") (pintype "bidirectional"))
      (node (ref "MOTOR_08") (pin "A2") (pinfunction "A2_A2") (pintype "bidirectional"))
    )
    (net (code "31") (name "MB1_01") (class "Default")
      (node (ref "CM_01") (pin "4") (pinfunction "4_4") (pintype "bidirectional"))
      (node (ref "MOTOR_01") (pin "B1") (pinfunction "B1_B1") (pintype "bidirectional"))
    )
    (net (code "32") (name "MB1_02") (class "Default")
      (node (ref "CM_02") (pin "4") (pinfunction "4_4") (pintype "bidirectional"))
      (node (ref "MOTOR_02") (pin "B1") (pinfunction "B1_B1") (pintype "bidirectional"))
    )
    (net (code "33") (name "MB1_03") (class "Default")
      (node (ref "CM_03") (pin "4") (pinfunction "4_4") (pintype "bidirectional"))
      (node (ref "MOTOR_03") (pin "B1") (pinfunction "B1_B1") (pintype "bidirectional"))
    )
    (net (code "34") (name "MB1_04") (class "Default")
      (node (ref "CM_04") (pin "4") (pinfunction "4_4") (pintype "bidirectional"))
      (node (ref "MOTOR_04") (pin "B1") (pinfunction "B1_B1") (pintype "bidirectional"))
    )
    (net (code "35") (name "MB1_05") (class "Default")
      (node (ref "CM_05") (pin "4") (pinfunction "4_4") (pintype "bidirectional"))
      (node (ref "MOTOR_05") (pin "B1") (pinfunction "B1_B1") (pintype "bidirectional"))
    )
    (net (code "36") (name "MB1_06") (class "Default")
      (node (ref "CM_06") (pin "4") (pinfunction "4_4") (pintype "bidirectional"))
      (node (ref "MOTOR_06") (pin "B1") (pinfunction "B1_B1") (pintype "bidirectional"))
    )
    (net (code "37") (name "MB1_07") (class "Default")
      (node (ref "CM_07") (pin "4") (pinfunction "4_4") (pintype "bidirectional"))
      (node (ref "MOTOR_07") (pin "B1") (pinfunction "B1_B1") (pintype "bidirectional"))
    )
    (net (code "38") (name "MB1_08") (class "Default")
      (node (ref "CM_08") (pin "4") (pinfunction "4_4") (pintype "bidirectional"))
      (node (ref "MOTOR_08") (pin "B1") (pinfunction "B1_B1") (pintype "bidirectional"))
    )
    (net (code "39") (name "MB2_01") (class "Default")
      (node (ref "CM_01") (pin "3") (pinfunction "3_3") (pintype "bidirectional"))
      (node (ref "MOTOR_01") (pin "B2") (pinfunction "B2_B2") (pintype "bidirectional"))
    )
    (net (code "40") (name "MB2_02") (class "Default")
      (node (ref "CM_02") (pin "3") (pinfunction "3_3") (pintype "bidirectional"))
      (node (ref "MOTOR_02") (pin "B2") (pinfunction "B2_B2") (pintype "bidirectional"))
    )
    (net (code "41") (name "MB2_03") (class "Default")
      (node (ref "CM_03") (pin "3") (pinfunction "3_3") (pintype "bidirectional"))
      (node (ref "MOTOR_03") (pin "B2") (pinfunction "B2_B2") (pintype "bidirectional"))
    )
    (net (code "42") (name "MB2_04") (class "Default")
      (node (ref "CM_04") (pin "3") (pinfunction "3_3") (pintype "bidirectional"))
      (node (ref "MOTOR_04") (pin "B2") (pinfunction "B2_B2") (pintype "bidirectional"))
    )
    (net (code "43") (name "MB2_05") (class "Default")
      (node (ref "CM_05") (pin "3") (pinfunction "3_3") (pintype "bidirectional"))
      (node (ref "MOTOR_05") (pin "B2") (pinfunction "B2_B2") (pintype "bidirectional"))
    )
    (net (code "44") (name "MB2_06") (class "Default")
      (node (ref "CM_06") (pin "3") (pinfunction "3_3") (pintype "bidirectional"))
      (node (ref "MOTOR_06") (pin "B2") (pinfunction "B2_B2") (pintype "bidirectional"))
    )
    (net (code "45") (name "MB2_07") (class "Default")
      (node (ref "CM_07") (pin "3") (pinfunction "3_3") (pintype "bidirectional"))
      (node (ref "MOTOR_07") (pin "B2") (pinfunction "B2_B2") (pintype "bidirectional"))
    )
    (net (code "46") (name "MB2_08") (class "Default")
      (node (ref "CM_08") (pin "3") (pinfunction "3_3") (pintype "bidirectional"))
      (node (ref "MOTOR_08") (pin "B2") (pinfunction "B2_B2") (pintype "bidirectional"))
    )
    (net (code "47") (name "MDIR_01") (class "Default")
      (node (ref "MOTOR_01") (pin "DIR") (pinfunction "DIR_DIR") (pintype "bidirectional"))
      (node (ref "U$3") (pin "6") (pinfunction "6_6") (pintype "bidirectional"))
    )
    (net (code "48") (name "MDIR_02") (class "Default")
      (node (ref "MOTOR_02") (pin "DIR") (pinfunction "DIR_DIR") (pintype "bidirectional"))
      (node (ref "U$3") (pin "8") (pinfunction "8/TX2_8") (pintype "bidirectional"))
    )
    (net (code "49") (name "MDIR_03") (class "Default")
      (node (ref "MOTOR_03") (pin "DIR") (pinfunction "DIR_DIR") (pintype "bidirectional"))
      (node (ref "U$3") (pin "10") (pinfunction "10/CS_10") (pintype "bidirectional"))
    )
    (net (code "50") (name "MDIR_04") (class "Default")
      (node (ref "MOTOR_04") (pin "DIR") (pinfunction "DIR_DIR") (pintype "bidirectional"))
      (node (ref "U$3") (pin "12") (pinfunction "12/MISO_12") (pintype "bidirectional"))
    )
    (net (code "51") (name "MDIR_05") (class "Default")
      (node (ref "MOTOR_05") (pin "DIR") (pinfunction "DIR_DIR") (pintype "bidirectional"))
      (node (ref "U$3") (pin "17/A3") (pinfunction "17/A3/SDA1_17/A3") (pintype "bidirectional"))
    )
    (net (code "52") (name "MDIR_06") (class "Default")
      (node (ref "MOTOR_06") (pin "DIR") (pinfunction "DIR_DIR") (pintype "bidirectional"))
      (node (ref "U$3") (pin "3") (pinfunction "3_3") (pintype "bidirectional"))
    )
    (net (code "53") (name "MDIR_07") (class "Default")
      (node (ref "MOTOR_07") (pin "DIR") (pinfunction "DIR_DIR") (pintype "bidirectional"))
      (node (ref "U$3") (pin "23/A9") (pinfunction "23/A9/CRX1_23/A9") (pintype "bidirectional"))
    )
    (net (code "54") (name "MDIR_08") (class "Default")
      (node (ref "MOTOR_08") (pin "DIR") (pinfunction "DIR_DIR") (pintype "bidirectional"))
      (node (ref "U$3") (pin "27") (pinfunction "27/A13/SCK1_27") (pintype "bidirectional"))
    )
    (net (code "55") (name "MOTOR_MUX_E") (class "Default")
      (node (ref "R14") (pin "1") (pinfunction "1_1") (pintype "passive"))
      (node (ref "U$3") (pin "15/A1") (pinfunction "15/A1/RX3_15/A1") (pintype "bidirectional"))
      (node (ref "U4") (pin "6") (pinfunction "~{E}_6") (pintype "bidirectional"))
    )
    (net (code "56") (name "MOTOR_MUX_RX") (class "Default")
      (node (ref "R15") (pin "1") (pinfunction "1_1") (pintype "passive"))
      (node (ref "U$3") (pin "21/A7") (pinfunction "21/A7/RX5_21/A7") (pintype "bidirectional"))
      (node (ref "U4") (pin "3") (pinfunction "Z_3") (pintype "bidirectional"))
    )
    (net (code "57") (name "MOTOR_MUX_TX") (class "Default")
      (node (ref "R15") (pin "2") (pinfunction "2_2") (pintype "passive"))
      (node (ref "U$3") (pin "20/A6") (pinfunction "20/A6/TX5_20/A6") (pintype "bidirectional"))
    )
    (net (code "58") (name "MOTOR_TX_RX_01") (class "Default")
      (node (ref "MOTOR_01") (pin "1") (pinfunction "1_1") (pintype "bidirectional"))
      (node (ref "U4") (pin "13") (pinfunction "Y0_13") (pintype "bidirectional"))
    )
    (net (code "59") (name "MOTOR_TX_RX_02") (class "Default")
      (node (ref "MOTOR_02") (pin "1") (pinfunction "1_1") (pintype "bidirectional"))
      (node (ref "U4") (pin "14") (pinfunction "Y1_14") (pintype "bidirectional"))
    )
    (net (code "60") (name "MOTOR_TX_RX_03") (class "Default")
      (node (ref "MOTOR_03") (pin "1") (pinfunction "1_1") (pintype "bidirectional"))
      (node (ref "U4") (pin "15") (pinfunction "Y2_15") (pintype "bidirectional"))
    )
    (net (code "61") (name "MOTOR_TX_RX_04") (class "Default")
      (node (ref "MOTOR_04") (pin "1") (pinfunction "1_1") (pintype "bidirectional"))
      (node (ref "U4") (pin "12") (pinfunction "Y3_12") (pintype "bidirectional"))
    )
    (net (code "62") (name "MOTOR_TX_RX_05") (class "Default")
      (node (ref "MOTOR_05") (pin "1") (pinfunction "1_1") (pintype "bidirectional"))
      (node (ref "U4") (pin "1") (pinfunction "Y4_1") (pintype "bidirectional"))
    )
    (net (code "63") (name "MOTOR_TX_RX_06") (class "Default")
      (node (ref "MOTOR_06") (pin "1") (pinfunction "1_1") (pintype "bidirectional"))
      (node (ref "U4") (pin "5") (pinfunction "Y5_5") (pintype "bidirectional"))
    )
    (net (code "64") (name "MOTOR_TX_RX_07") (class "Default")
      (node (ref "MOTOR_07") (pin "1") (pinfunction "1_1") (pintype "bidirectional"))
      (node (ref "U4") (pin "2") (pinfunction "Y6_2") (pintype "bidirectional"))
    )
    (net (code "65") (name "MOTOR_TX_RX_08") (class "Default")
      (node (ref "MOTOR_08") (pin "1") (pinfunction "1_1") (pintype "bidirectional"))
      (node (ref "U4") (pin "4") (pinfunction "Y7_4") (pintype "bidirectional"))
    )
    (net (code "66") (name "MSTEP_01") (class "Default")
      (node (ref "MOTOR_01") (pin "STEP") (pinfunction "STEP_STEP") (pintype "bidirectional"))
      (node (ref "U$3") (pin "5") (pinfunction "5_5") (pintype "bidirectional"))
    )
    (net (code "67") (name "MSTEP_02") (class "Default")
      (node (ref "MOTOR_02") (pin "STEP") (pinfunction "STEP_STEP") (pintype "bidirectional"))
      (node (ref "U$3") (pin "7") (pinfunction "7/RX2_7") (pintype "bidirectional"))
    )
    (net (code "68") (name "MSTEP_03") (class "Default")
      (node (ref "MOTOR_03") (pin "STEP") (pinfunction "STEP_STEP") (pintype "bidirectional"))
      (node (ref "U$3") (pin "9") (pinfunction "9_9") (pintype "bidirectional"))
    )
    (net (code "69") (name "MSTEP_04") (class "Default")
      (node (ref "MOTOR_04") (pin "STEP") (pinfunction "STEP_STEP") (pintype "bidirectional"))
      (node (ref "U$3") (pin "11") (pinfunction "11/MOSI_11") (pintype "bidirectional"))
    )
    (net (code "70") (name "MSTEP_05") (class "Default")
      (node (ref "MOTOR_05") (pin "STEP") (pinfunction "STEP_STEP") (pintype "bidirectional"))
      (node (ref "U$3") (pin "16/A2") (pinfunction "16/A2/SCL1_16/A2") (pintype "bidirectional"))
    )
    (net (code "71") (name "MSTEP_06") (class "Default")
      (node (ref "MOTOR_06") (pin "STEP") (pinfunction "STEP_STEP") (pintype "bidirectional"))
      (node (ref "U$3") (pin "2") (pinfunction "2_2") (pintype "bidirectional"))
    )
    (net (code "72") (name "MSTEP_07") (class "Default")
      (node (ref "MOTOR_07") (pin "STEP") (pinfunction "STEP_STEP") (pintype "bidirectional"))
      (node (ref "U$3") (pin "22/A8") (pinfunction "22/A8/CTX1_22/A8") (pintype "bidirectional"))
    )
    (net (code "73") (name "MSTEP_08") (class "Default")
      (node (ref "MOTOR_08") (pin "STEP") (pinfunction "STEP_STEP") (pintype "bidirectional"))
      (node (ref "U$3") (pin "26") (pinfunction "26/A12/MOSI1_26") (pintype "bidirectional"))
    )
    (net (code "74") (name "NEOPIXEL_01_5V") (class "Default")
      (node (ref "P1") (pin "1") (pinfunction "1_1") (pintype "passive"))
      (node (ref "U3") (pin "13") (pinfunction "Y0_13") (pintype "bidirectional"))
    )
    (net (code "75") (name "NEOPIXEL_02_5V") (class "Default")
      (node (ref "P1") (pin "3") (pinfunction "3_3") (pintype "passive"))
      (node (ref "U3") (pin "14") (pinfunction "Y1_14") (pintype "bidirectional"))
    )
    (net (code "76") (name "NEOPIXEL_03_5V") (class "Default")
      (node (ref "P1") (pin "5") (pinfunction "5_5") (pintype "passive"))
      (node (ref "U3") (pin "15") (pinfunction "Y2_15") (pintype "bidirectional"))
    )
    (net (code "77") (name "NEOPIXEL_04_5V") (class "Default")
      (node (ref "P1") (pin "7") (pinfunction "7_7") (pintype "passive"))
      (node (ref "U3") (pin "12") (pinfunction "Y3_12") (pintype "bidirectional"))
    )
    (net (code "78") (name "NEOPIXEL_05_5V") (class "Default")
      (node (ref "P1") (pin "9") (pinfunction "9_9") (pintype "passive"))
      (node (ref "U3") (pin "1") (pinfunction "Y4_1") (pintype "bidirectional"))
    )
    (net (code "79") (name "NEOPIXEL_06_5V") (class "Default")
      (node (ref "P1") (pin "11") (pinfunction "11_11") (pintype "passive"))
      (node (ref "U3") (pin "5") (pinfunction "Y5_5") (pintype "bidirectional"))
    )
    (net (code "80") (name "NEOPIXEL_07_5V") (class "Default")
      (node (ref "P1") (pin "13") (pinfunction "13_13") (pintype "passive"))
      (node (ref "U3") (pin "2") (pinfunction "Y6_2") (pintype "bidirectional"))
    )
    (net (code "81") (name "NEOPIXEL_08_5V") (class "Default")
      (node (ref "P1") (pin "15") (pinfunction "15_15") (pintype "passive"))
      (node (ref "U3") (pin "4") (pinfunction "Y7_4") (pintype "bidirectional"))
    )
    (net (code "82") (name "NEO_5V_Z") (class "Default")
      (node (ref "IC1") (pin "4") (pinfunction "Y_4") (pintype "bidirectional"))
      (node (ref "R12") (pin "1") (pinfunction "1_1") (pintype "passive"))
    )
    (net (code "83") (name "NEO_MUX_E") (class "Default")
      (node (ref "R13") (pin "1") (pinfunction "1_1") (pintype "passive"))
      (node (ref "U$3") (pin "4") (pinfunction "4_4") (pintype "bidirectional"))
      (node (ref "U3") (pin "6") (pinfunction "~{E}_6") (pintype "bidirectional"))
    )
    (net (code "84") (name "NEO_TX3") (class "Default")
      (node (ref "IC1") (pin "2") (pinfunction "A_2") (pintype "bidirectional"))
      (node (ref "U$3") (pin "14/A0") (pinfunction "14/A0/TX3_14/A0") (pintype "bidirectional"))
    )
    (net (code "85") (name "Net-(CAN_INPUT-1)") (class "Default")
      (node (ref "CAN_INPUT") (pin "2") (pinfunction "1_2") (pintype "passive"))
      (node (ref "CAN_INPUT1") (pin "2") (pinfunction "1_2") (pintype "passive"))
      (node (ref "J2") (pin "2") (pinfunction "2_2") (pintype "passive"))
      (node (ref "MCP2562FD") (pin "6") (pinfunction "CANL_6") (pintype "input"))
      (node (ref "PES_D3") (pin "2") (pinfunction "2_2") (pintype "passive"))
    )
    (net (code "86") (name "Net-(CAN_INPUT-2)") (class "Default")
      (node (ref "CAN_INPUT") (pin "1") (pinfunction "2_1") (pintype "passive"))
      (node (ref "CAN_INPUT1") (pin "1") (pinfunction "2_1") (pintype "passive"))
      (node (ref "MCP2562FD") (pin "7") (pinfunction "CANH_7") (pintype "input"))
      (node (ref "PES_D3") (pin "1") (pinfunction "1_1") (pintype "passive"))
      (node (ref "R8") (pin "1") (pinfunction "1_1") (pintype "passive"))
    )
    (net (code "87") (name "Net-(CAN_INPUT4-1)") (class "Default")
      (node (ref "CAN_INPUT4") (pin "2") (pinfunction "1_2") (pintype "passive"))
      (node (ref "CAN_INPUT5") (pin "2") (pinfunction "1_2") (pintype "passive"))
      (node (ref "J3") (pin "2") (pinfunction "2_2") (pintype "passive"))
      (node (ref "MCP2562_2.0") (pin "6") (pinfunction "CANL_6") (pintype "input"))
      (node (ref "PES_D5") (pin "2") (pinfunction "2_2") (pintype "passive"))
    )
    (net (code "88") (name "Net-(CAN_INPUT4-2)") (class "Default")
      (node (ref "CAN_INPUT4") (pin "1") (pinfunction "2_1") (pintype "passive"))
      (node (ref "CAN_INPUT5") (pin "1") (pinfunction "2_1") (pintype "passive"))
      (node (ref "MCP2562_2.0") (pin "7") (pinfunction "CANH_7") (pintype "input"))
      (node (ref "PES_D5") (pin "1") (pinfunction "1_1") (pintype "passive"))
      (node (ref "R4") (pin "1") (pinfunction "1_1") (pintype "passive"))
    )
    (net (code "89") (name "Net-(IC1-OE)") (class "Default")
      (node (ref "IC1") (pin "1") (pinfunction "OE_1") (pintype "bidirectional"))
      (node (ref "R20") (pin "1") (pinfunction "1_1") (pintype "passive"))
    )
    (net (code "90") (name "Net-(J2-Pad1)") (class "Default")
      (node (ref "J2") (pin "1") (pinfunction "1_1") (pintype "passive"))
      (node (ref "R8") (pin "2") (pinfunction "2_2") (pintype "passive"))
    )
    (net (code "91") (name "Net-(J3-Pad1)") (class "Default")
      (node (ref "J3") (pin "1") (pinfunction "1_1") (pintype "passive"))
      (node (ref "R4") (pin "2") (pinfunction "2_2") (pintype "passive"))
    )
    (net (code "92") (name "Net-(STATUS_LED-A)") (class "Default")
      (node (ref "R10") (pin "1") (pinfunction "1_1") (pintype "passive"))
      (node (ref "STATUS_LED") (pin "1") (pinfunction "A_1") (pintype "passive"))
    )
    (net (code "93") (name "Net-(U1-EN)") (class "Default")
      (node (ref "R9") (pin "2") (pinfunction "2_2") (pintype "passive"))
      (node (ref "U1") (pin "3") (pinfunction "EN_3") (pintype "bidirectional"))
    )
    (net (code "94") (name "Net-(U1-~{FAULT})") (class "Default")
      (node (ref "R11") (pin "2") (pinfunction "2_2") (pintype "passive"))
      (node (ref "U1") (pin "4") (pinfunction "~{FAULT}_4") (pintype "bidirectional"))
    )
    (net (code "95") (name "Net-(U3-Z)") (class "Default")
      (node (ref "R12") (pin "2") (pinfunction "2_2") (pintype "passive"))
      (node (ref "U3") (pin "3") (pinfunction "Z_3") (pintype "bidirectional"))
    )
    (net (code "96") (name "OSCIO") (class "Default")
      (node (ref "SX1509") (pin "11") (pinfunction "OSCIO_11") (pintype "bidirectional"))
    )
    (net (code "97") (name "RESET") (class "Default")
      (node (ref "P1") (pin "10") (pinfunction "10_10") (pintype "passive"))
      (node (ref "U$3") (pin "RESET") (pinfunction "RESET_RESET") (pintype "bidirectional"))
    )
    (net (code "98") (name "STATUS_PIN") (class "Default")
      (node (ref "P1") (pin "12") (pinfunction "12_12") (pintype "passive"))
      (node (ref "R10") (pin "2") (pinfunction "2_2") (pintype "passive"))
    )
    (net (code "99") (name "SX00_0") (class "Default")
      (node (ref "MOTOR_06") (pin "ENA") (pinfunction "ENABLE_ENA") (pintype "bidirectional"))
      (node (ref "SX1509") (pin "27") (pinfunction "I/O[0]_27") (pintype "bidirectional"))
    )
    (net (code "100") (name "SX00_1") (class "Default")
      (node (ref "J1") (pin "6") (pinfunction "6_6") (pintype "passive"))
      (node (ref "SX1509") (pin "28") (pinfunction "I/O[1]_28") (pintype "bidirectional"))
    )
    (net (code "101") (name "SX00_2") (class "Default")
      (node (ref "MOTOR_04") (pin "ENA") (pinfunction "ENABLE_ENA") (pintype "bidirectional"))
      (node (ref "SX1509") (pin "1") (pinfunction "I/O[2]_1") (pintype "bidirectional"))
    )
    (net (code "102") (name "SX00_3") (class "Default")
      (node (ref "J4") (pin "3") (pinfunction "3_3") (pintype "passive"))
      (node (ref "SX1509") (pin "2") (pinfunction "I/O[3]_2") (pintype "bidirectional"))
    )
    (net (code "103") (name "SX00_4") (class "Default")
      (node (ref "MOTOR_03") (pin "ENA") (pinfunction "ENABLE_ENA") (pintype "bidirectional"))
      (node (ref "SX1509") (pin "5") (pinfunction "I/O[4]_5") (pintype "bidirectional"))
    )
    (net (code "104") (name "SX00_5") (class "Default")
      (node (ref "J4") (pin "4") (pinfunction "4_4") (pintype "passive"))
      (node (ref "SX1509") (pin "6") (pinfunction "I/O[5]_6") (pintype "bidirectional"))
      (node (ref "U4") (pin "11") (pinfunction "S0_11") (pintype "bidirectional"))
    )
    (net (code "105") (name "SX00_6") (class "Default")
      (node (ref "MOTOR_02") (pin "ENA") (pinfunction "ENABLE_ENA") (pintype "bidirectional"))
      (node (ref "SX1509") (pin "7") (pinfunction "I/O[6]_7") (pintype "bidirectional"))
    )
    (net (code "106") (name "SX00_7") (class "Default")
      (node (ref "J4") (pin "5") (pinfunction "5_5") (pintype "passive"))
      (node (ref "SX1509") (pin "8") (pinfunction "I/O[7]_8") (pintype "bidirectional"))
      (node (ref "U4") (pin "10") (pinfunction "S1_10") (pintype "bidirectional"))
    )
    (net (code "107") (name "SX00_8") (class "Default")
      (node (ref "MOTOR_05") (pin "ENA") (pinfunction "ENABLE_ENA") (pintype "bidirectional"))
      (node (ref "SX1509") (pin "13") (pinfunction "I/O[8]_13") (pintype "bidirectional"))
    )
    (net (code "108") (name "SX00_9") (class "Default")
      (node (ref "J4") (pin "6") (pinfunction "6_6") (pintype "passive"))
      (node (ref "SX1509") (pin "14") (pinfunction "I/O[9]_14") (pintype "bidirectional"))
      (node (ref "U4") (pin "9") (pinfunction "S2_9") (pintype "bidirectional"))
    )
    (net (code "109") (name "SX00_10") (class "Default")
      (node (ref "MOTOR_01") (pin "ENA") (pinfunction "ENABLE_ENA") (pintype "bidirectional"))
      (node (ref "SX1509") (pin "15") (pinfunction "I/O[10]_15") (pintype "bidirectional"))
    )
    (net (code "110") (name "SX00_11") (class "Default")
      (node (ref "SX1509") (pin "16") (pinfunction "I/O[11]_16") (pintype "bidirectional"))
      (node (ref "U3") (pin "11") (pinfunction "S0_11") (pintype "bidirectional"))
    )
    (net (code "111") (name "SX00_12") (class "Default")
      (node (ref "MOTOR_07") (pin "ENA") (pinfunction "ENABLE_ENA") (pintype "bidirectional"))
      (node (ref "SX1509") (pin "19") (pinfunction "I/O[12]_19") (pintype "bidirectional"))
    )
    (net (code "112") (name "SX00_13") (class "Default")
      (node (ref "SX1509") (pin "20") (pinfunction "I/O[13]_20") (pintype "bidirectional"))
      (node (ref "U3") (pin "10") (pinfunction "S1_10") (pintype "bidirectional"))
    )
    (net (code "113") (name "SX00_14") (class "Default")
      (node (ref "MOTOR_08") (pin "ENA") (pinfunction "ENABLE_ENA") (pintype "bidirectional"))
      (node (ref "SX1509") (pin "21") (pinfunction "I/O[14]_21") (pintype "bidirectional"))
    )
    (net (code "114") (name "SX00_15") (class "Default")
      (node (ref "SX1509") (pin "22") (pinfunction "I/O[15]_22") (pintype "bidirectional"))
      (node (ref "U3") (pin "9") (pinfunction "S2_9") (pintype "bidirectional"))
    )
    (net (code "115") (name "SX00_ADDR0") (class "Default")
      (node (ref "JP5") (pin "1") (pinfunction "1_1") (pintype "passive"))
      (node (ref "SX1509") (pin "26") (pinfunction "ADDR0_26") (pintype "bidirectional"))
    )
    (net (code "116") (name "SX00_ADDR1") (class "Default")
      (node (ref "JP6") (pin "2") (pinfunction "2_2") (pintype "passive"))
      (node (ref "SX1509") (pin "10") (pinfunction "ADDR1_10") (pintype "bidirectional"))
    )
    (net (code "117") (name "SX00_SCL") (class "Default")
      (node (ref "P1") (pin "4") (pinfunction "4_4") (pintype "passive"))
      (node (ref "R5") (pin "1") (pinfunction "1_1") (pintype "passive"))
      (node (ref "SX1509") (pin "25") (pinfunction "SCL_25") (pintype "bidirectional"))
      (node (ref "U$3") (pin "19/A5") (pinfunction "19/A5/SCL0_19/A5") (pintype "bidirectional"))
    )
    (net (code "118") (name "SX00_SDA") (class "Default")
      (node (ref "P1") (pin "2") (pinfunction "2_2") (pintype "passive"))
      (node (ref "R2") (pin "1") (pinfunction "1_1") (pintype "passive"))
      (node (ref "SX1509") (pin "24") (pinfunction "SDA_24") (pintype "bidirectional"))
      (node (ref "U$3") (pin "18/A4") (pinfunction "18/A4/SDA0_18/A4") (pintype "bidirectional"))
    )
    (net (code "119") (name "VBAT") (class "Default")
      (node (ref "U$3") (pin "VBAT") (pinfunction "VBAT_VBAT") (pintype "power_in"))
    )
    (net (code "120") (name "VCC_5VREG") (class "Default")
      (node (ref "C10") (pin "1") (pinfunction "1_1") (pintype "passive"))
      (node (ref "C11") (pin "1") (pinfunction "1_1") (pintype "passive"))
      (node (ref "C4") (pin "1") (pinfunction "1_1") (pintype "passive"))
      (node (ref "C8") (pin "1") (pinfunction "1_1") (pintype "passive"))
      (node (ref "D2") (pin "A") (pinfunction "A_A") (pintype "passive"))
      (node (ref "D3") (pin "A") (pinfunction "A_A") (pintype "passive"))
      (node (ref "D4") (pin "A") (pinfunction "A_A") (pintype "passive"))
      (node (ref "D5") (pin "A") (pinfunction "A_A") (pintype "passive"))
      (node (ref "D6") (pin "A") (pinfunction "A_A") (pintype "passive"))
      (node (ref "D7") (pin "A") (pinfunction "A_A") (pintype "passive"))
      (node (ref "D8") (pin "A") (pinfunction "A_A") (pintype "passive"))
      (node (ref "D9") (pin "A") (pinfunction "A_A") (pintype "passive"))
      (node (ref "IC1") (pin "5") (pinfunction "VCC_5") (pintype "bidirectional"))
      (node (ref "J1") (pin "2") (pinfunction "2_2") (pintype "passive"))
      (node (ref "J4") (pin "2") (pinfunction "2_2") (pintype "passive"))
      (node (ref "MCP2562FD") (pin "3") (pinfunction "VDD_3") (pintype "power_in"))
      (node (ref "MCP2562_2.0") (pin "3") (pinfunction "VDD_3") (pintype "power_in"))
      (node (ref "MOTOR_01") (pin "FAULT") (pinfunction "FAULT_FAULT") (pintype "bidirectional"))
      (node (ref "MOTOR_02") (pin "FAULT") (pinfunction "FAULT_FAULT") (pintype "bidirectional"))
      (node (ref "MOTOR_03") (pin "FAULT") (pinfunction "FAULT_FAULT") (pintype "bidirectional"))
      (node (ref "MOTOR_04") (pin "FAULT") (pinfunction "FAULT_FAULT") (pintype "bidirectional"))
      (node (ref "MOTOR_05") (pin "FAULT") (pinfunction "FAULT_FAULT") (pintype "bidirectional"))
      (node (ref "MOTOR_06") (pin "FAULT") (pinfunction "FAULT_FAULT") (pintype "bidirectional"))
      (node (ref "MOTOR_07") (pin "FAULT") (pinfunction "FAULT_FAULT") (pintype "bidirectional"))
      (node (ref "MOTOR_08") (pin "FAULT") (pinfunction "FAULT_FAULT") (pintype "bidirectional"))
      (node (ref "U$3") (pin "VIN") (pinfunction "VIN_VIN") (pintype "power_in"))
      (node (ref "U1") (pin "6") (pinfunction "VOUT_6") (pintype "bidirectional"))
      (node (ref "U3") (pin "16") (pinfunction "VCC_16") (pintype "bidirectional"))
      (node (ref "U3") (pin "EP") (pinfunction "VCC_EP") (pintype "bidirectional"))
      (node (ref "U4") (pin "16") (pinfunction "VCC_16") (pintype "bidirectional"))
      (node (ref "U4") (pin "EP") (pinfunction "VCC_EP") (pintype "bidirectional"))
    )
    (net (code "121") (name "VCC_LEDS") (class "Default")
      (node (ref "D1") (pin "C") (pinfunction "C_C") (pintype "passive"))
      (node (ref "P1") (pin "17") (pinfunction "17_17") (pintype "passive"))
      (node (ref "R1") (pin "1") (pinfunction "1_1") (pintype "passive"))
    )
    (net (code "122") (name "VCC_M") (class "Default")
      (node (ref "C12") (pin "2") (pinfunction "2_2") (pintype "passive"))
      (node (ref "C13") (pin "2") (pinfunction "2_2") (pintype "passive"))
      (node (ref "C14") (pin "2") (pinfunction "2_2") (pintype "passive"))
      (node (ref "C15") (pin "2") (pinfunction "2_2") (pintype "passive"))
      (node (ref "C16") (pin "2") (pinfunction "2_2") (pintype "passive"))
      (node (ref "C17") (pin "2") (pinfunction "2_2") (pintype "passive"))
      (node (ref "C18") (pin "2") (pinfunction "2_2") (pintype "passive"))
      (node (ref "C19") (pin "2") (pinfunction "2_2") (pintype "passive"))
      (node (ref "D2") (pin "C") (pinfunction "C_C") (pintype "passive"))
      (node (ref "D3") (pin "C") (pinfunction "C_C") (pintype "passive"))
      (node (ref "D4") (pin "C") (pinfunction "C_C") (pintype "passive"))
      (node (ref "D5") (pin "C") (pinfunction "C_C") (pintype "passive"))
      (node (ref "D6") (pin "C") (pinfunction "C_C") (pintype "passive"))
      (node (ref "D7") (pin "C") (pinfunction "C_C") (pintype "passive"))
      (node (ref "D8") (pin "C") (pinfunction "C_C") (pintype "passive"))
      (node (ref "D9") (pin "C") (pinfunction "C_C") (pintype "passive"))
      (node (ref "MC1") (pin "+") (pinfunction "+_+") (pintype "passive"))
      (node (ref "MC2") (pin "+") (pinfunction "+_+") (pintype "passive"))
      (node (ref "MC3") (pin "+") (pinfunction "+_+") (pintype "passive"))
      (node (ref "MC4") (pin "+") (pinfunction "+_+") (pintype "passive"))
      (node (ref "MC5") (pin "+") (pinfunction "+_+") (pintype "passive"))
      (node (ref "MC6") (pin "+") (pinfunction "+_+") (pintype "passive"))
      (node (ref "MC7") (pin "+") (pinfunction "+_+") (pintype "passive"))
      (node (ref "MC8") (pin "+") (pinfunction "+_+") (pintype "passive"))
      (node (ref "MOTOR_01") (pin "VM") (pinfunction "VM_VM") (pintype "bidirectional"))
      (node (ref "MOTOR_02") (pin "VM") (pinfunction "VM_VM") (pintype "bidirectional"))
      (node (ref "MOTOR_03") (pin "VM") (pinfunction "VM_VM") (pintype "bidirectional"))
      (node (ref "MOTOR_04") (pin "VM") (pinfunction "VM_VM") (pintype "bidirectional"))
      (node (ref "MOTOR_05") (pin "VM") (pinfunction "VM_VM") (pintype "bidirectional"))
      (node (ref "MOTOR_06") (pin "VM") (pinfunction "VM_VM") (pintype "bidirectional"))
      (node (ref "MOTOR_07") (pin "VM") (pinfunction "VM_VM") (pintype "bidirectional"))
      (node (ref "MOTOR_08") (pin "VM") (pinfunction "VM_VM") (pintype "bidirectional"))
      (node (ref "POWER_M") (pin "1") (pinfunction "1_1") (pintype "passive"))
    )
    (net (code "123") (name "VCC_MCU") (class "Default")
      (node (ref "POWER_MCU") (pin "1") (pinfunction "1_1") (pintype "passive"))
      (node (ref "U$1") (pin "VIN_1") (pinfunction "P$1_VIN_1") (pintype "bidirectional"))
      (node (ref "U$1") (pin "VIN_2") (pinfunction "P$1_VIN_2") (pintype "bidirectional"))
    )
    (net (code "124") (name "VCC_SWITCH") (class "Default")
      (node (ref "C1") (pin "1") (pinfunction "1_1") (pintype "passive"))
      (node (ref "C7") (pin "1") (pinfunction "1_1") (pintype "passive"))
      (node (ref "R1") (pin "2") (pinfunction "2_2") (pintype "passive"))
      (node (ref "R11") (pin "1") (pinfunction "1_1") (pintype "passive"))
      (node (ref "R9") (pin "1") (pinfunction "1_1") (pintype "passive"))
      (node (ref "U$1") (pin "VOUT_1") (pinfunction "P$4_VOUT_1") (pintype "bidirectional"))
      (node (ref "U$1") (pin "VOUT_2") (pinfunction "P$4_VOUT_2") (pintype "bidirectional"))
      (node (ref "U1") (pin "1") (pinfunction "VIN_1") (pintype "bidirectional"))
    )
    (net (code "125") (name "unconnected-(MOTOR_01-MODE1-PadMS1)") (class "Default")
      (node (ref "MOTOR_01") (pin "MS1") (pinfunction "MODE1_MS1") (pintype "bidirectional"))
    )
    (net (code "126") (name "unconnected-(MOTOR_01-MODE2-PadMS2)") (class "Default")
      (node (ref "MOTOR_01") (pin "MS2") (pinfunction "MODE2_MS2") (pintype "bidirectional"))
    )
    (net (code "127") (name "unconnected-(MOTOR_01-Pad2)") (class "Default")
      (node (ref "MOTOR_01") (pin "2") (pinfunction "2_2") (pintype "bidirectional"))
    )
    (net (code "128") (name "unconnected-(MOTOR_01-PadSTBY)") (class "Default")
      (node (ref "MOTOR_01") (pin "STBY") (pinfunction "STBY_STBY") (pintype "bidirectional"))
    )
    (net (code "129") (name "unconnected-(MOTOR_02-MODE1-PadMS1)") (class "Default")
      (node (ref "MOTOR_02") (pin "MS1") (pinfunction "MODE1_MS1") (pintype "bidirectional"))
    )
    (net (code "130") (name "unconnected-(MOTOR_02-MODE2-PadMS2)") (class "Default")
      (node (ref "MOTOR_02") (pin "MS2") (pinfunction "MODE2_MS2") (pintype "bidirectional"))
    )
    (net (code "131") (name "unconnected-(MOTOR_02-Pad2)") (class "Default")
      (node (ref "MOTOR_02") (pin "2") (pinfunction "2_2") (pintype "bidirectional"))
    )
    (net (code "132") (name "unconnected-(MOTOR_02-PadSTBY)") (class "Default")
      (node (ref "MOTOR_02") (pin "STBY") (pinfunction "STBY_STBY") (pintype "bidirectional"))
    )
    (net (code "133") (name "unconnected-(MOTOR_03-MODE1-PadMS1)") (class "Default")
      (node (ref "MOTOR_03") (pin "MS1") (pinfunction "MODE1_MS1") (pintype "bidirectional"))
    )
    (net (code "134") (name "unconnected-(MOTOR_03-MODE2-PadMS2)") (class "Default")
      (node (ref "MOTOR_03") (pin "MS2") (pinfunction "MODE2_MS2") (pintype "bidirectional"))
    )
    (net (code "135") (name "unconnected-(MOTOR_03-Pad2)") (class "Default")
      (node (ref "MOTOR_03") (pin "2") (pinfunction "2_2") (pintype "bidirectional"))
    )
    (net (code "136") (name "unconnected-(MOTOR_03-PadSTBY)") (class "Default")
      (node (ref "MOTOR_03") (pin "STBY") (pinfunction "STBY_STBY") (pintype "bidirectional"))
    )
    (net (code "137") (name "unconnected-(MOTOR_04-MODE1-PadMS1)") (class "Default")
      (node (ref "MOTOR_04") (pin "MS1") (pinfunction "MODE1_MS1") (pintype "bidirectional"))
    )
    (net (code "138") (name "unconnected-(MOTOR_04-MODE2-PadMS2)") (class "Default")
      (node (ref "MOTOR_04") (pin "MS2") (pinfunction "MODE2_MS2") (pintype "bidirectional"))
    )
    (net (code "139") (name "unconnected-(MOTOR_04-Pad2)") (class "Default")
      (node (ref "MOTOR_04") (pin "2") (pinfunction "2_2") (pintype "bidirectional"))
    )
    (net (code "140") (name "unconnected-(MOTOR_04-PadSTBY)") (class "Default")
      (node (ref "MOTOR_04") (pin "STBY") (pinfunction "STBY_STBY") (pintype "bidirectional"))
    )
    (net (code "141") (name "unconnected-(MOTOR_05-MODE1-PadMS1)") (class "Default")
      (node (ref "MOTOR_05") (pin "MS1") (pinfunction "MODE1_MS1") (pintype "bidirectional"))
    )
    (net (code "142") (name "unconnected-(MOTOR_05-MODE2-PadMS2)") (class "Default")
      (node (ref "MOTOR_05") (pin "MS2") (pinfunction "MODE2_MS2") (pintype "bidirectional"))
    )
    (net (code "143") (name "unconnected-(MOTOR_05-Pad2)") (class "Default")
      (node (ref "MOTOR_05") (pin "2") (pinfunction "2_2") (pintype "bidirectional"))
    )
    (net (code "144") (name "unconnected-(MOTOR_05-PadSTBY)") (class "Default")
      (node (ref "MOTOR_05") (pin "STBY") (pinfunction "STBY_STBY") (pintype "bidirectional"))
    )
    (net (code "145") (name "unconnected-(MOTOR_06-MODE1-PadMS1)") (class "Default")
      (node (ref "MOTOR_06") (pin "MS1") (pinfunction "MODE1_MS1") (pintype "bidirectional"))
    )
    (net (code "146") (name "unconnected-(MOTOR_06-MODE2-PadMS2)") (class "Default")
      (node (ref "MOTOR_06") (pin "MS2") (pinfunction "MODE2_MS2") (pintype "bidirectional"))
    )
    (net (code "147") (name "unconnected-(MOTOR_06-Pad2)") (class "Default")
      (node (ref "MOTOR_06") (pin "2") (pinfunction "2_2") (pintype "bidirectional"))
    )
    (net (code "148") (name "unconnected-(MOTOR_06-PadSTBY)") (class "Default")
      (node (ref "MOTOR_06") (pin "STBY") (pinfunction "STBY_STBY") (pintype "bidirectional"))
    )
    (net (code "149") (name "unconnected-(MOTOR_07-MODE1-PadMS1)") (class "Default")
      (node (ref "MOTOR_07") (pin "MS1") (pinfunction "MODE1_MS1") (pintype "bidirectional"))
    )
    (net (code "150") (name "unconnected-(MOTOR_07-MODE2-PadMS2)") (class "Default")
      (node (ref "MOTOR_07") (pin "MS2") (pinfunction "MODE2_MS2") (pintype "bidirectional"))
    )
    (net (code "151") (name "unconnected-(MOTOR_07-Pad2)") (class "Default")
      (node (ref "MOTOR_07") (pin "2") (pinfunction "2_2") (pintype "bidirectional"))
    )
    (net (code "152") (name "unconnected-(MOTOR_07-PadSTBY)") (class "Default")
      (node (ref "MOTOR_07") (pin "STBY") (pinfunction "STBY_STBY") (pintype "bidirectional"))
    )
    (net (code "153") (name "unconnected-(MOTOR_08-MODE1-PadMS1)") (class "Default")
      (node (ref "MOTOR_08") (pin "MS1") (pinfunction "MODE1_MS1") (pintype "bidirectional"))
    )
    (net (code "154") (name "unconnected-(MOTOR_08-MODE2-PadMS2)") (class "Default")
      (node (ref "MOTOR_08") (pin "MS2") (pinfunction "MODE2_MS2") (pintype "bidirectional"))
    )
    (net (code "155") (name "unconnected-(MOTOR_08-Pad2)") (class "Default")
      (node (ref "MOTOR_08") (pin "2") (pinfunction "2_2") (pintype "bidirectional"))
    )
    (net (code "156") (name "unconnected-(MOTOR_08-PadSTBY)") (class "Default")
      (node (ref "MOTOR_08") (pin "STBY") (pinfunction "STBY_STBY") (pintype "bidirectional"))
    )
    (net (code "157") (name "unconnected-(U$1-P$3-PadON)") (class "Default")
      (node (ref "U$1") (pin "ON") (pinfunction "P$3_ON") (pintype "bidirectional"))
    )
    (net (code "158") (name "unconnected-(U$1-P$6-PadGND_5)") (class "Default")
      (node (ref "U$1") (pin "GND_5") (pinfunction "P$6_GND_5") (pintype "bidirectional"))
    )
    (net (code "159") (name "unconnected-(U$3-PadPGM)") (class "Default")
      (node (ref "U$3") (pin "PGM") (pinfunction "PGM_PGM") (pintype "bidirectional"))
    )
    (net (code "160") (name "unconnected-(U1-CSLEW-Pad5)") (class "Default")
      (node (ref "U1") (pin "5") (pinfunction "CSLEW_5") (pintype "bidirectional"))
    )
    (net (code "161") (name "~{RESET}") (class "Default")
      (node (ref "R3") (pin "1") (pinfunction "1_1") (pintype "passive"))
      (node (ref "SX1509") (pin "23") (pinfunction "~{RESET}_23") (pintype "bidirectional"))
    )
  )
)
